# EvaluationBoard.net
KiCad netlist of a schematic drawn in EAGLE
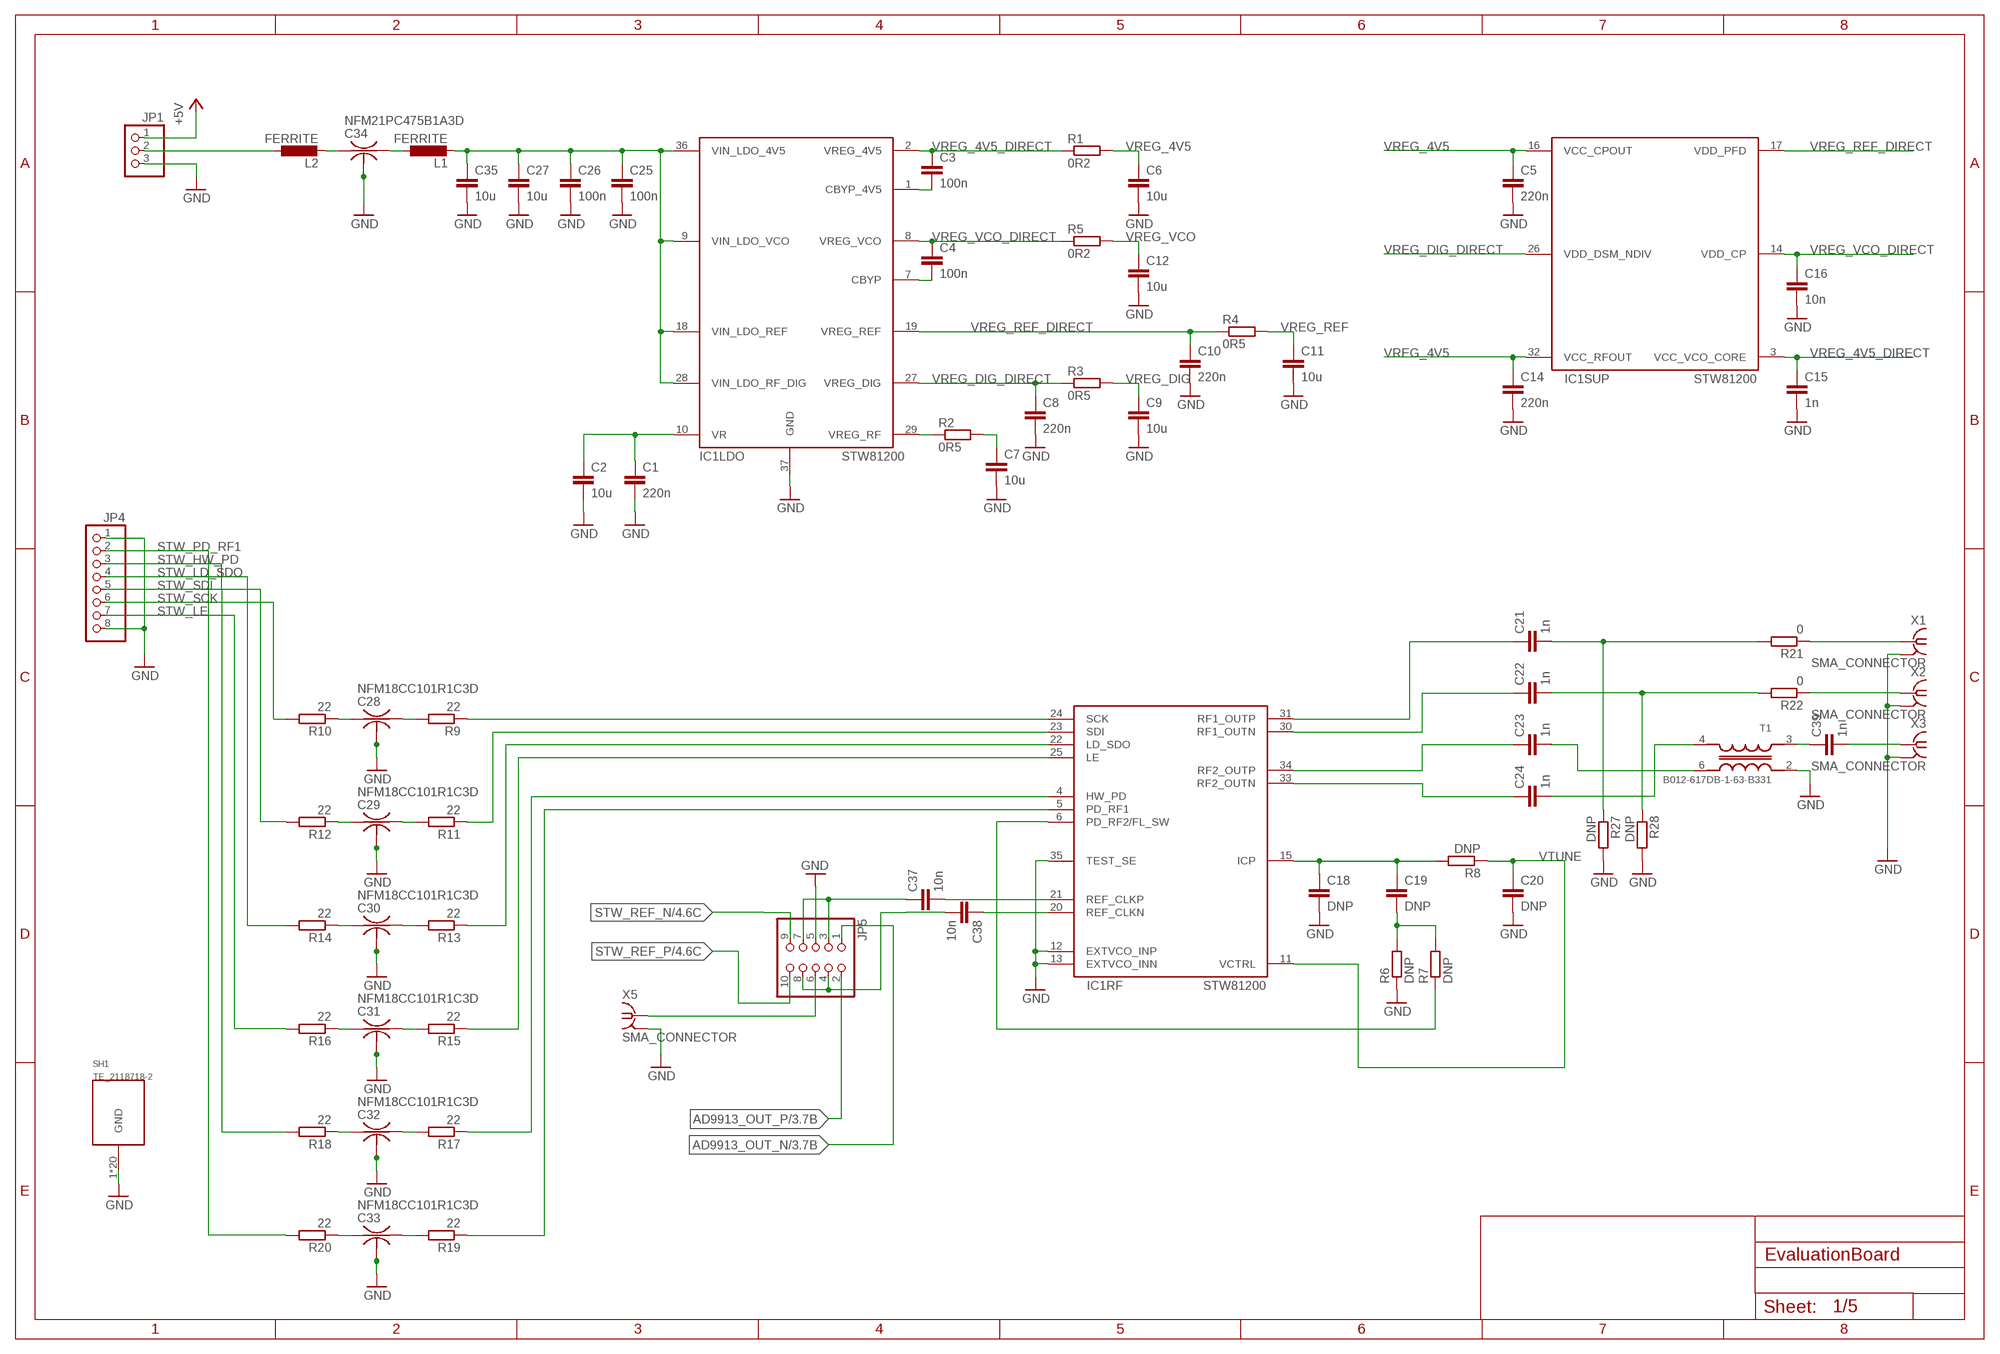
[diagram p0: schematic, sheet 1]
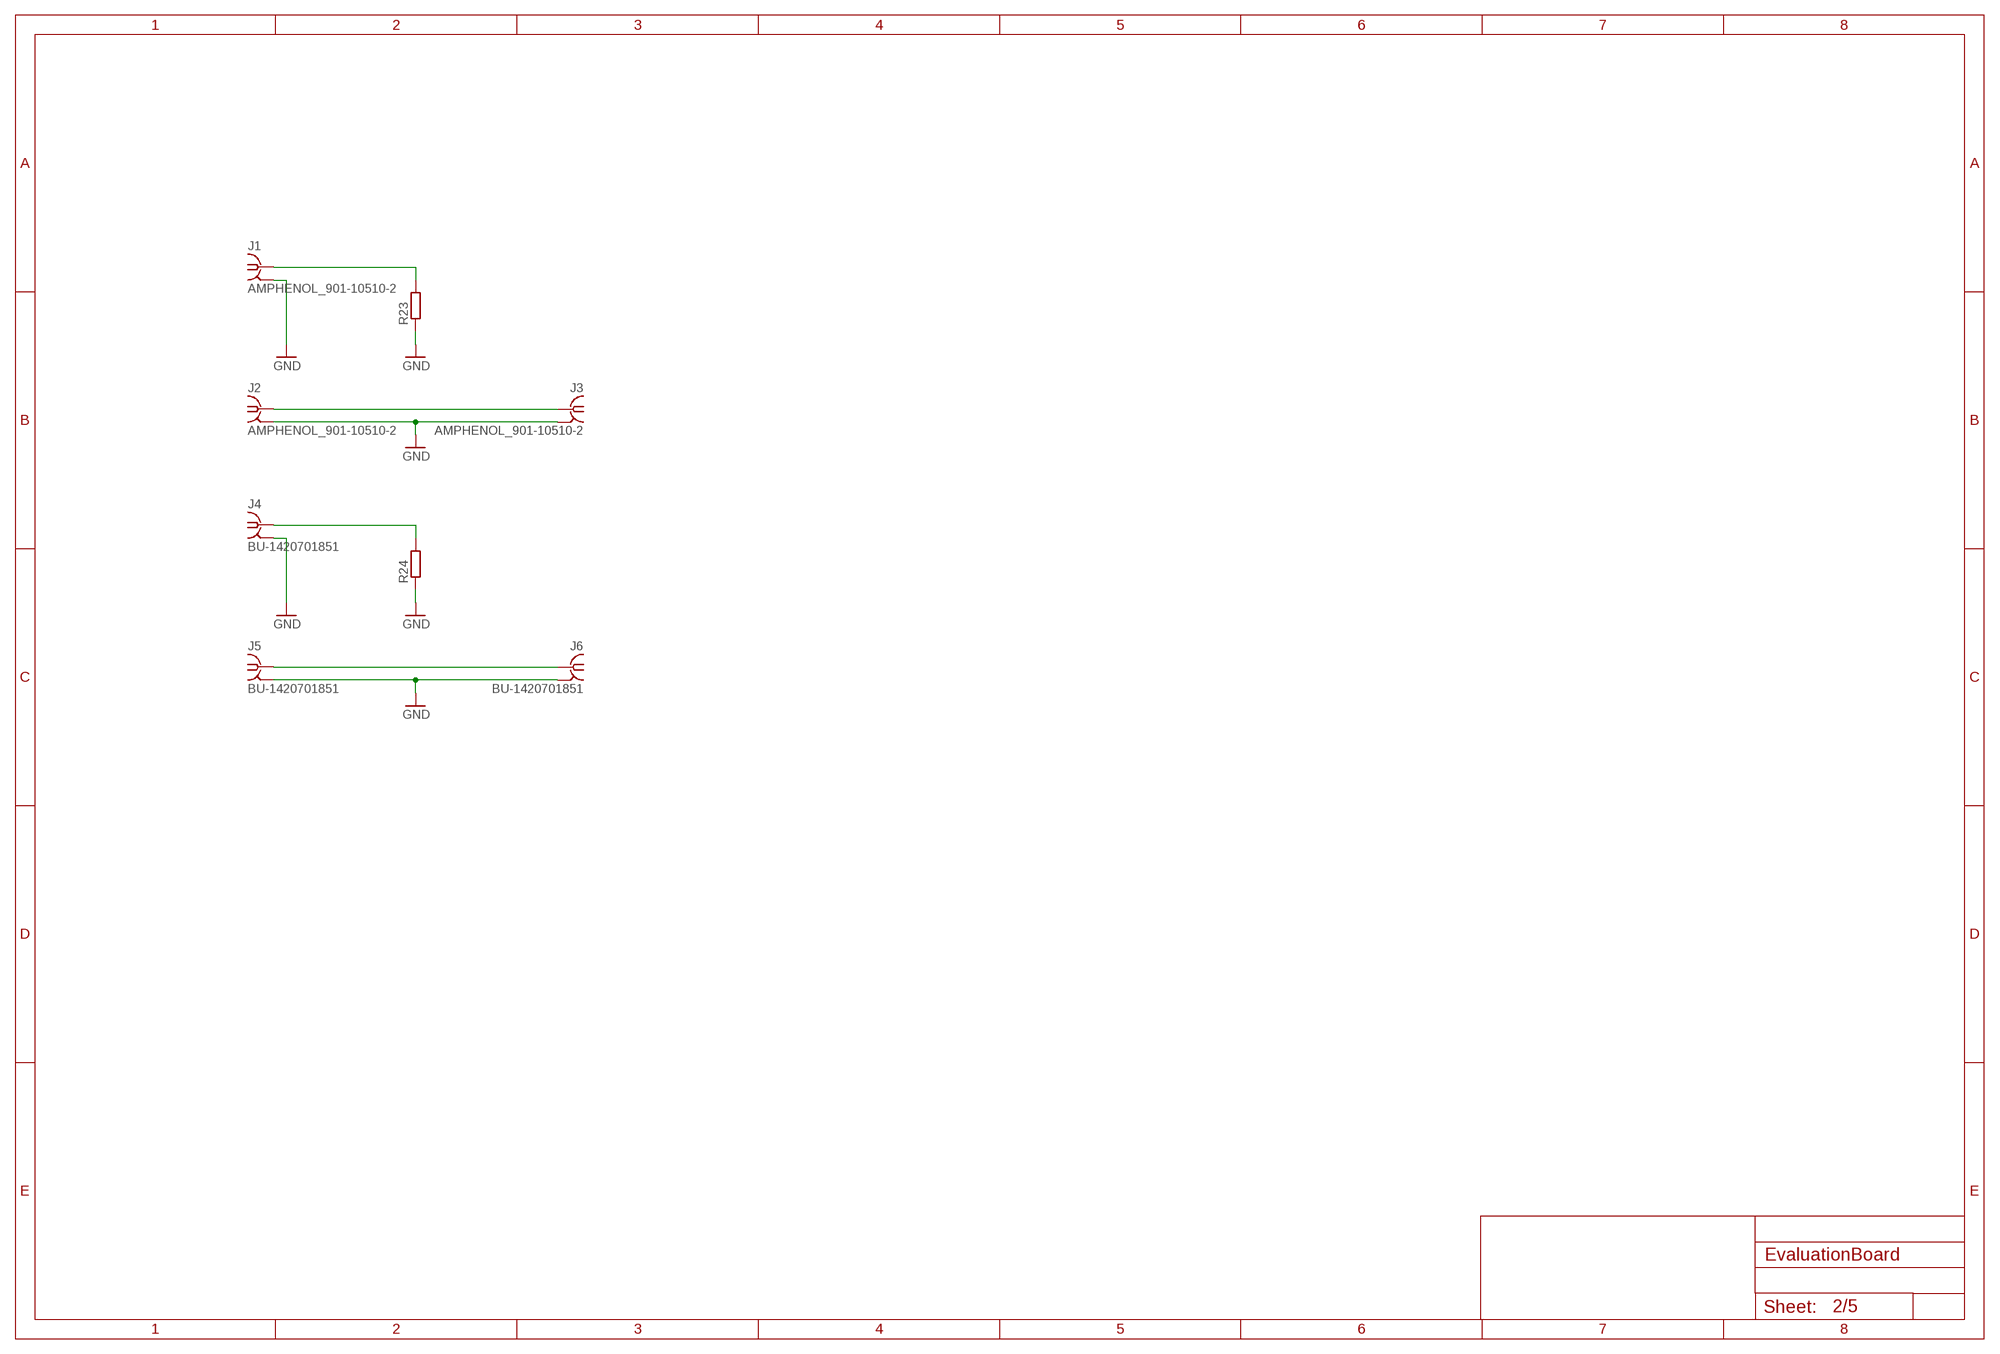
[diagram p1: schematic, sheet 2]
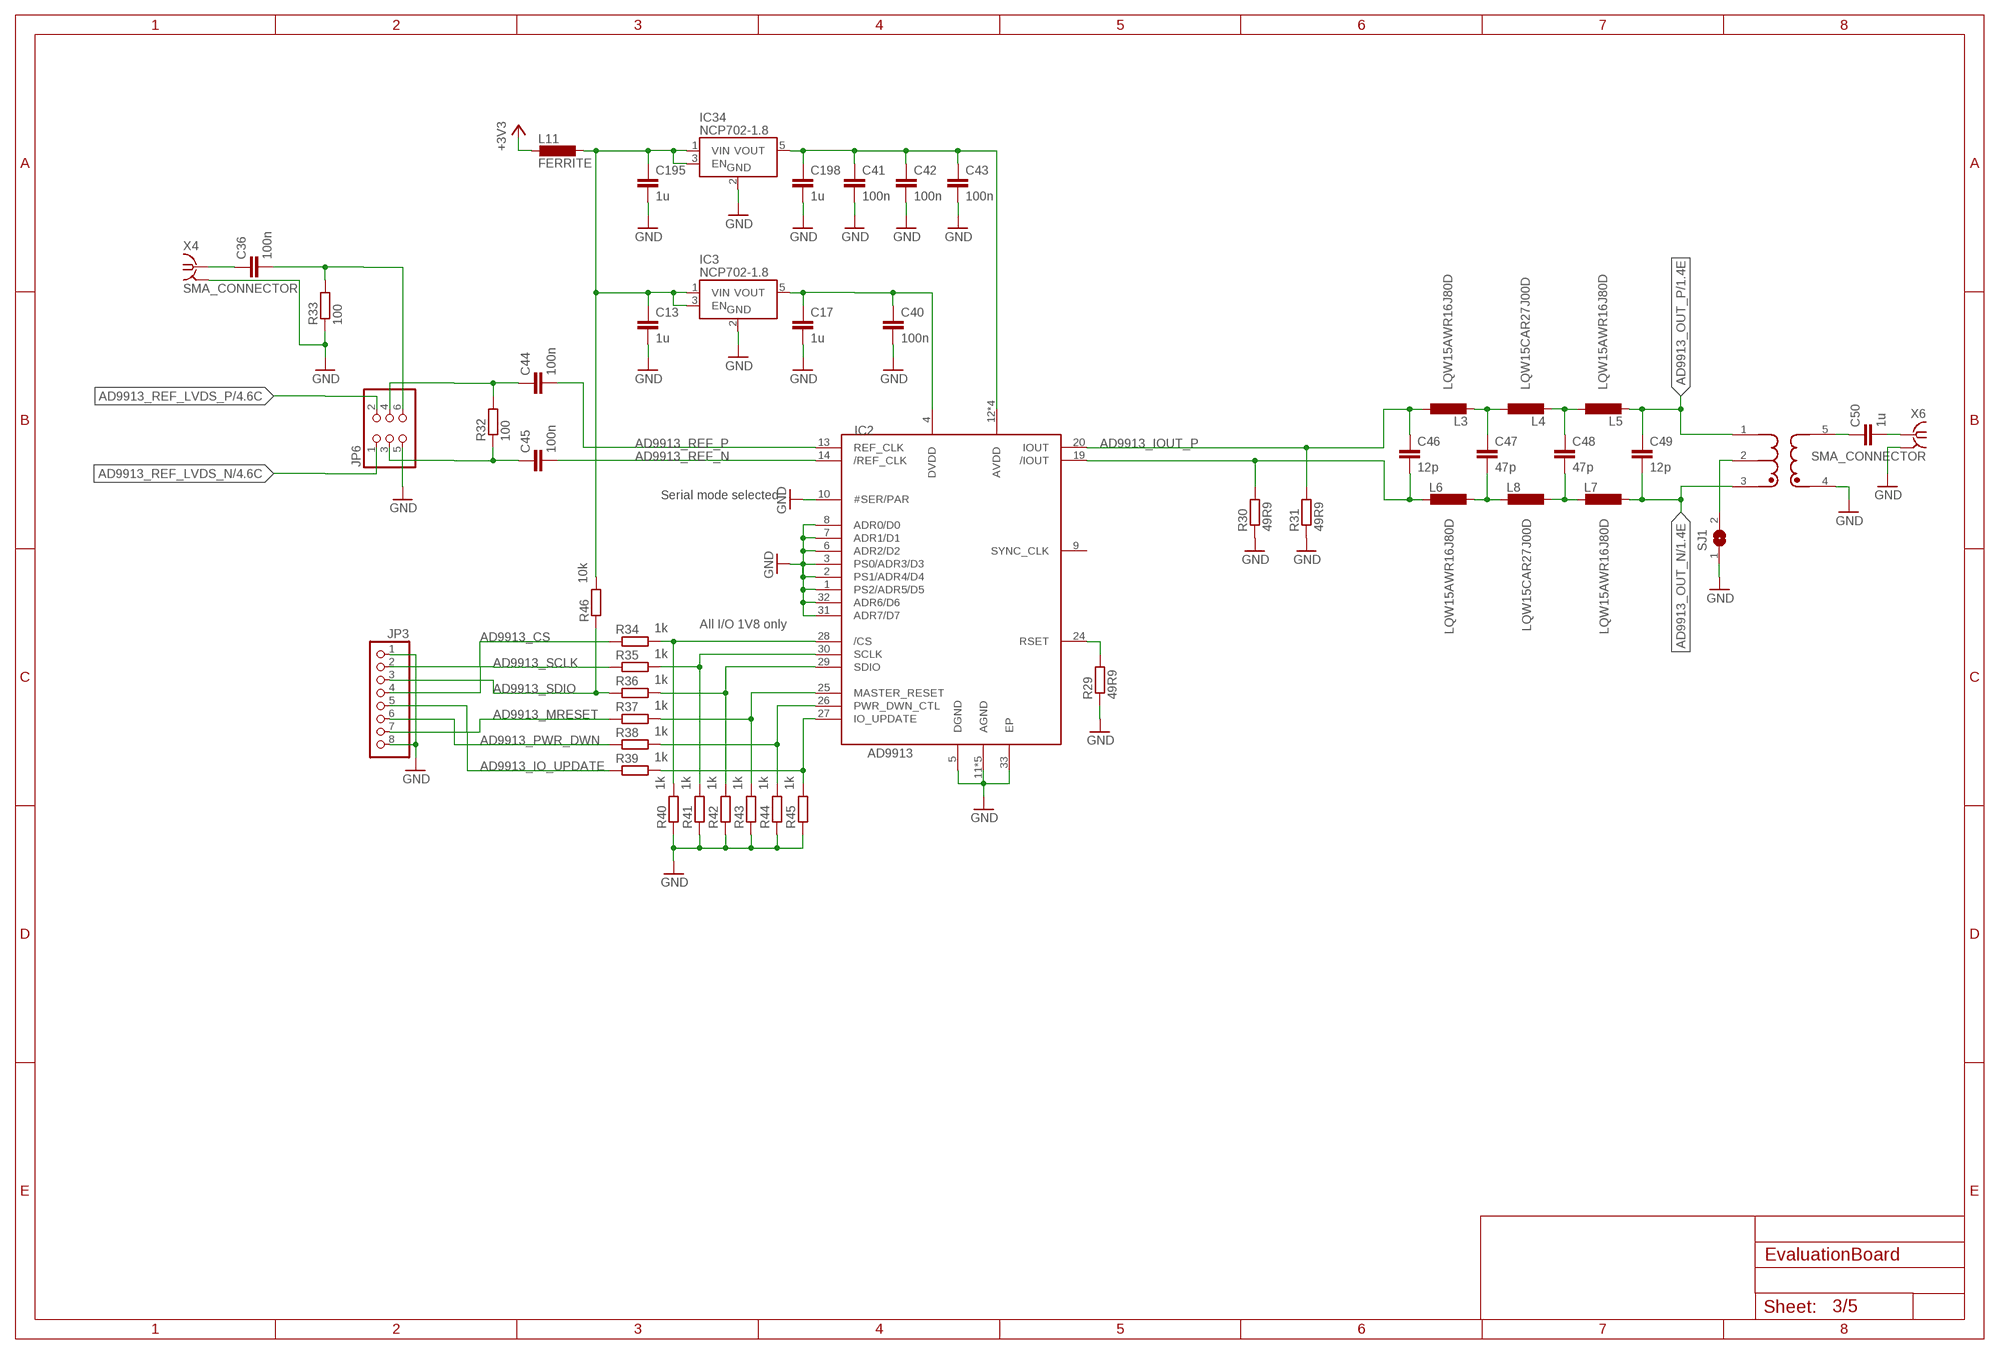
[diagram p2: schematic, sheet 3]
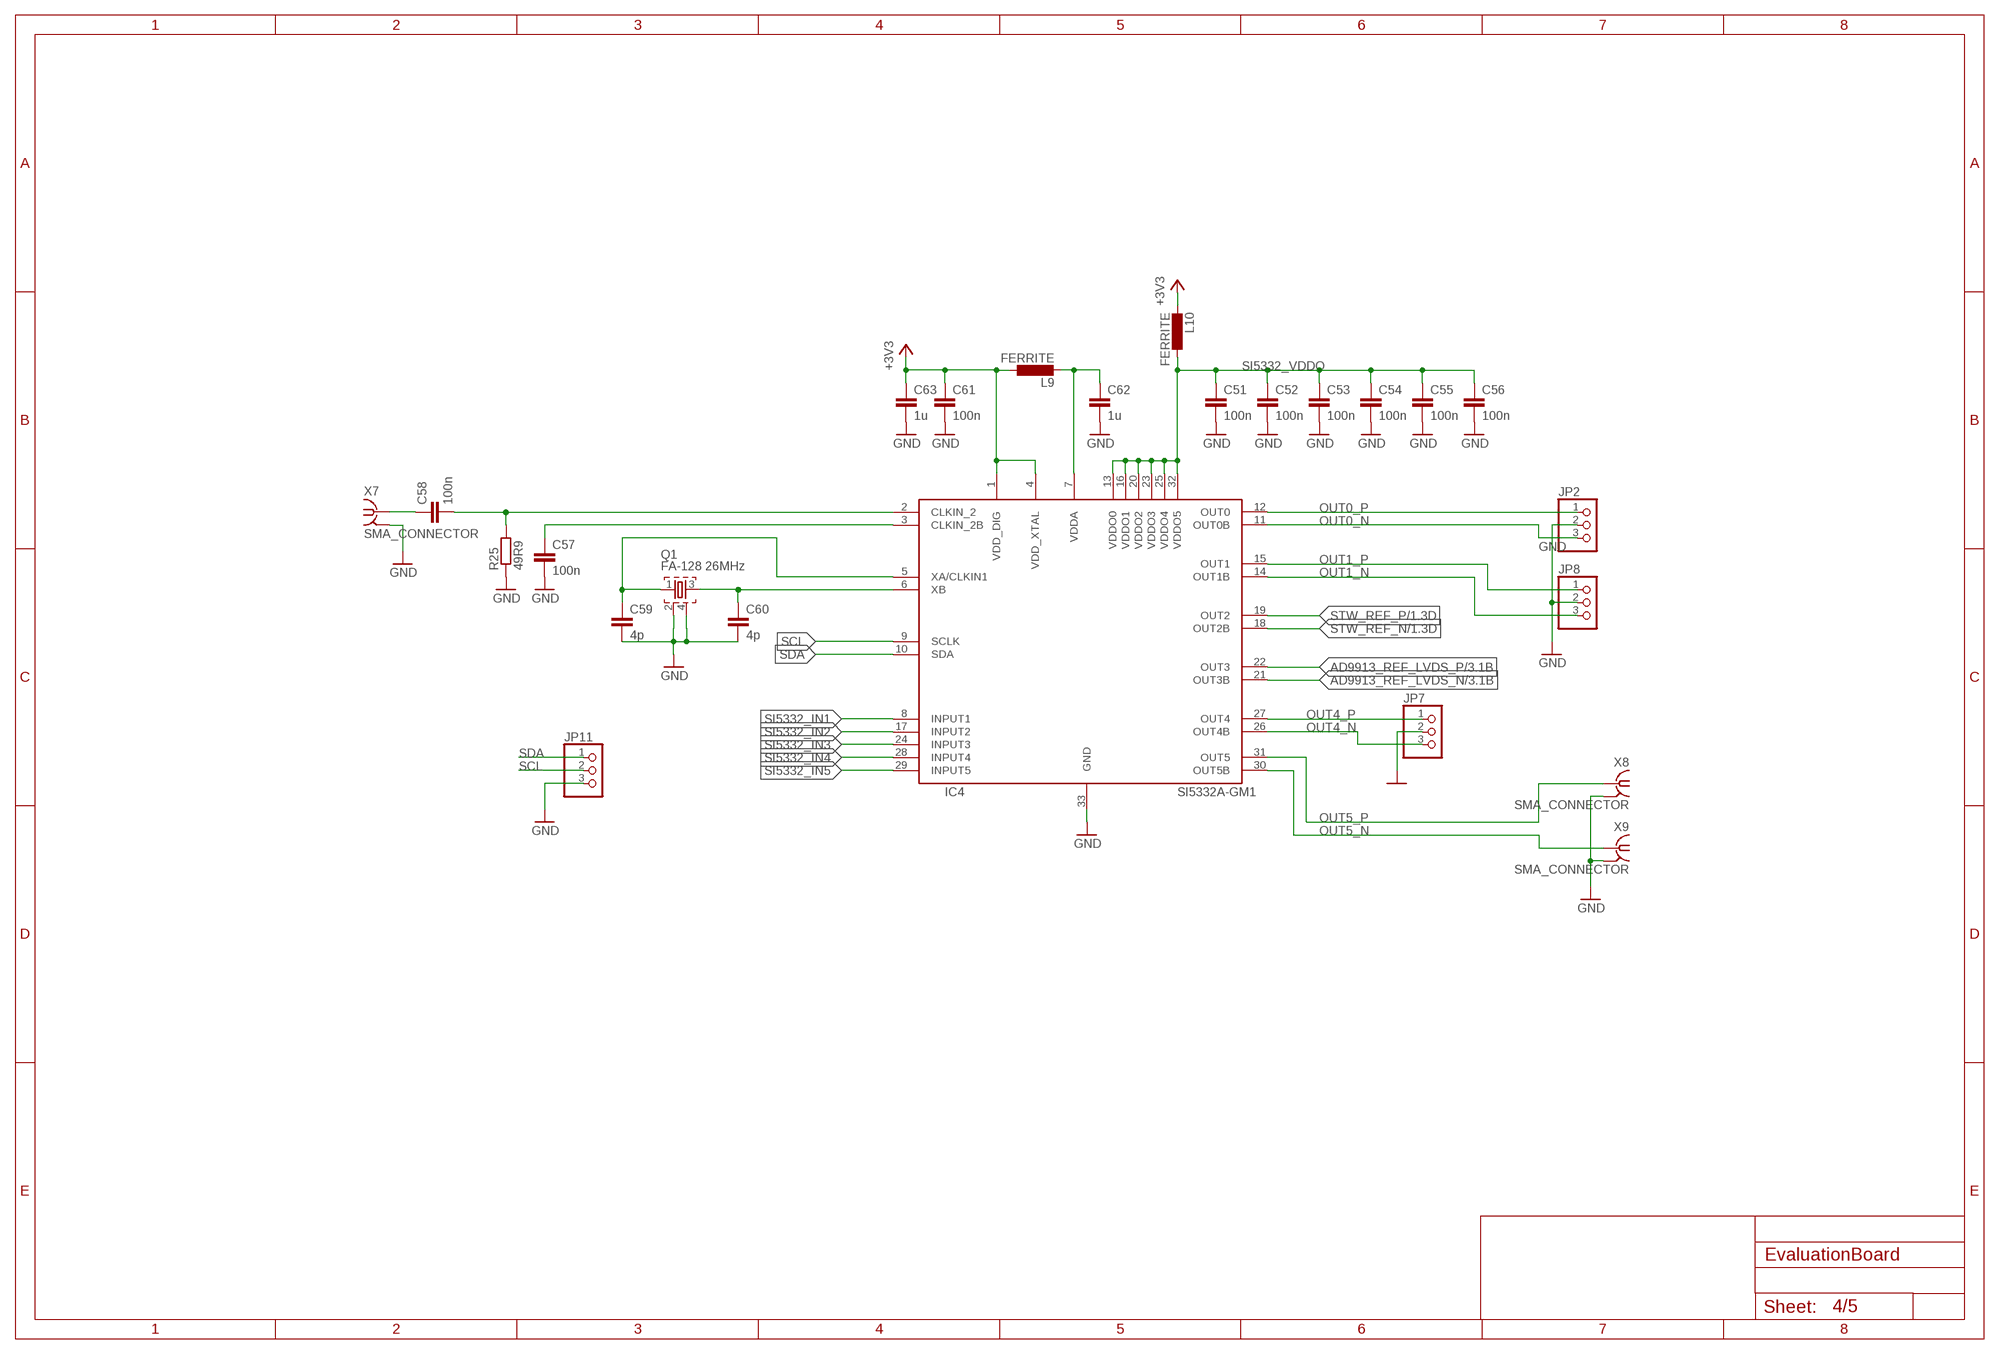
[diagram p3: schematic, sheet 4]
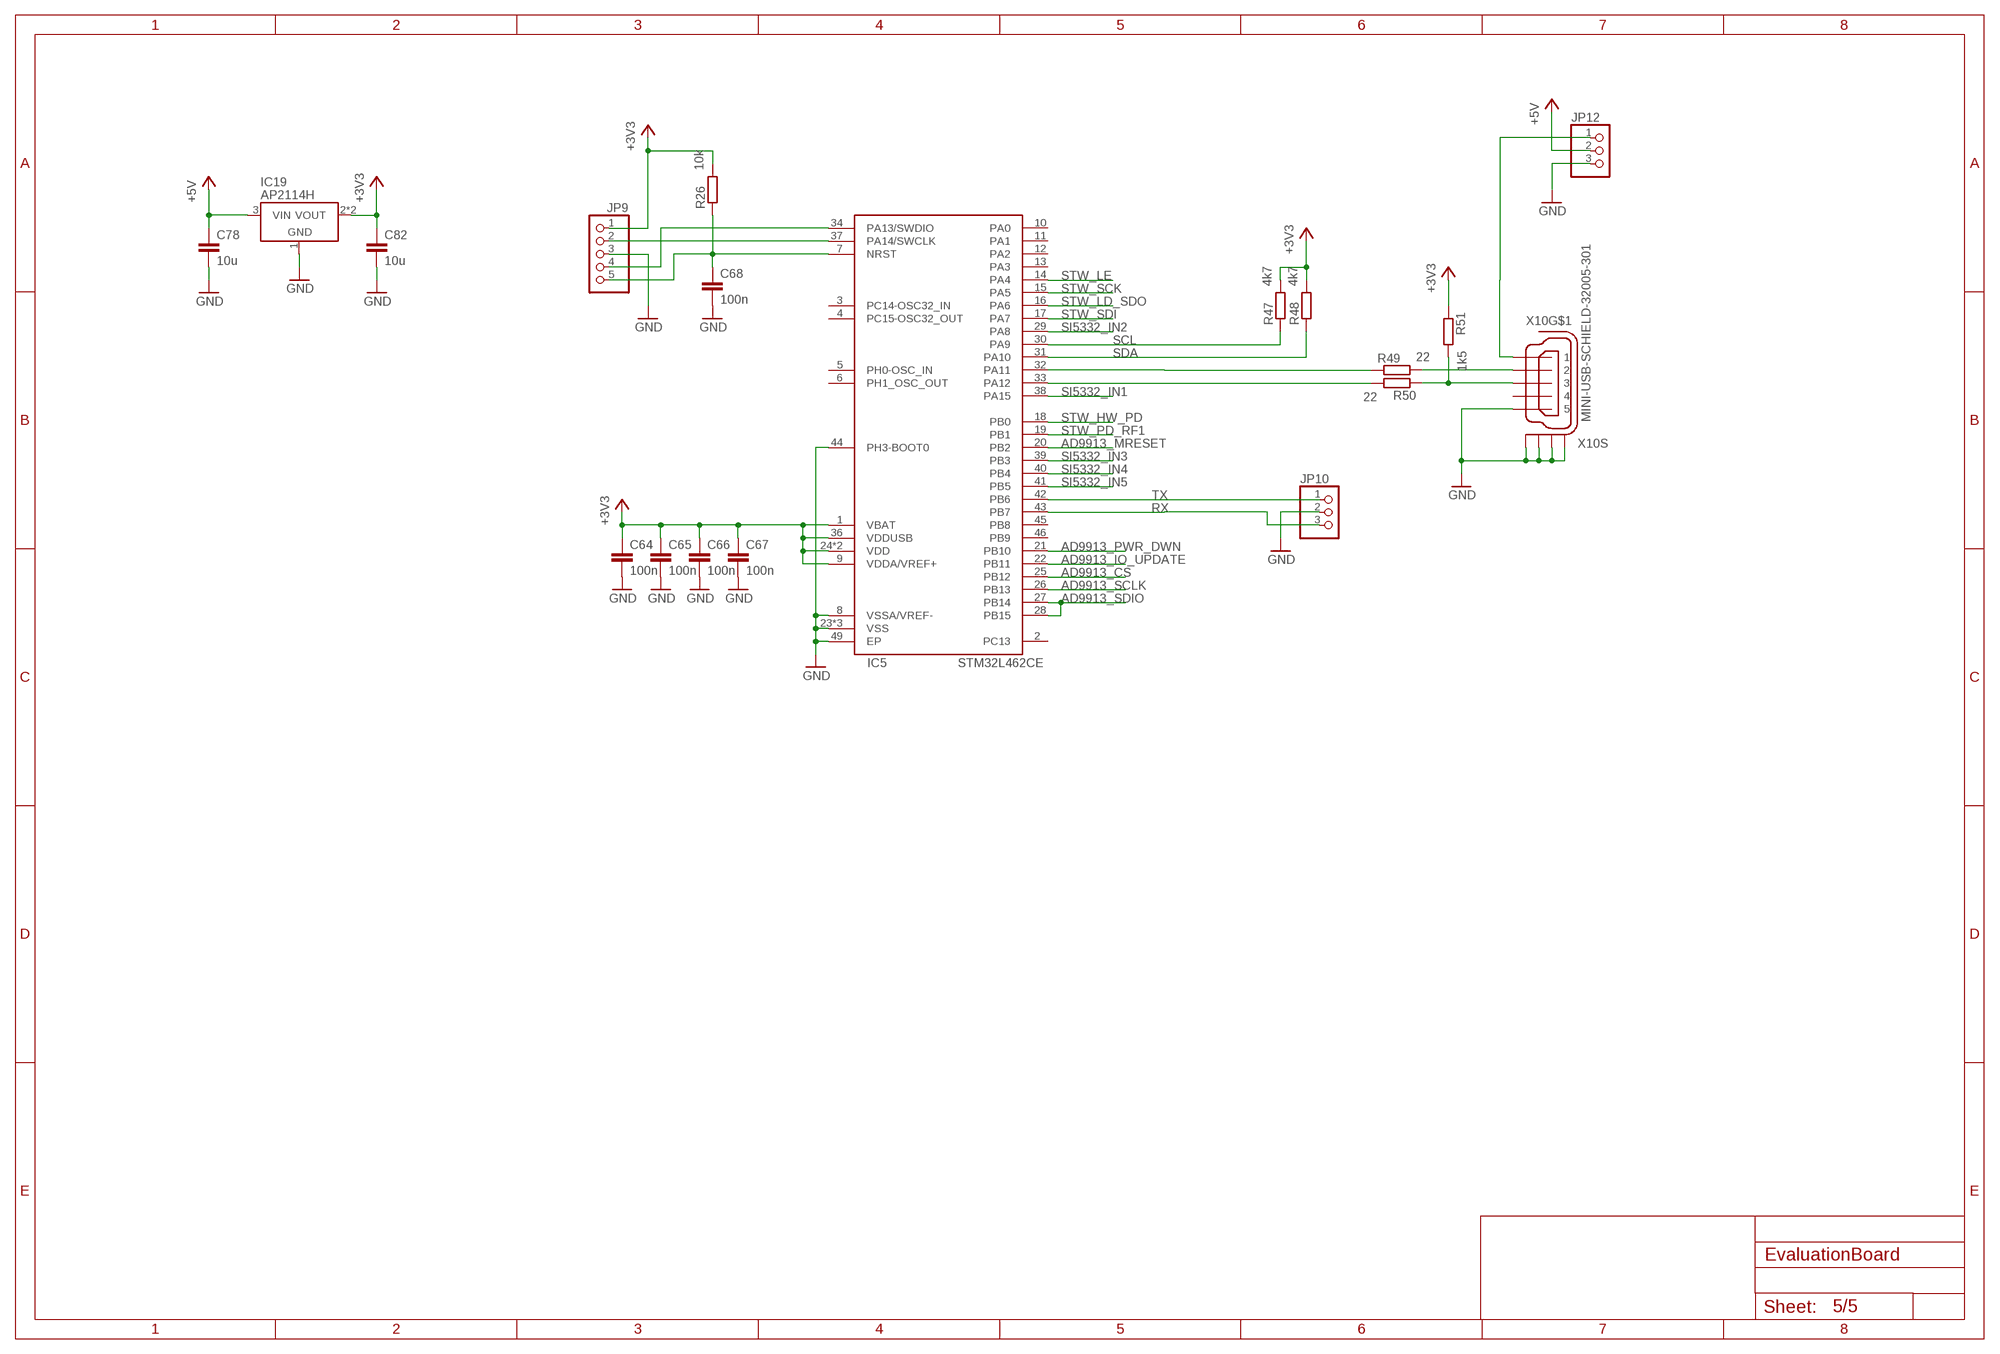
[diagram p4: schematic, sheet 5]

(export (version "E")
  (design (tool "Eeschema 10.0.6"))
  (components
    (comp (ref "C64")
      (value "100n")
      (footprint "eagle-import:C0402")
      (libsource (lib "eagle-import") (part "C-EU?{colon}2C0402"))
    )
    (comp (ref "C65")
      (value "100n")
      (footprint "eagle-import:C0402")
      (libsource (lib "eagle-import") (part "C-EU?{colon}2C0402"))
    )
    (comp (ref "C66")
      (value "100n")
      (footprint "eagle-import:C0402")
      (libsource (lib "eagle-import") (part "C-EU?{colon}2C0402"))
    )
    (comp (ref "C67")
      (value "100n")
      (footprint "eagle-import:C0402")
      (libsource (lib "eagle-import") (part "C-EU?{colon}2C0402"))
    )
    (comp (ref "C68")
      (value "100n")
      (footprint "eagle-import:C0402")
      (libsource (lib "eagle-import") (part "C-EU?{colon}2C0402"))
    )
    (comp (ref "C78")
      (value "10u")
      (footprint "eagle-import:C1206")
      (libsource (lib "eagle-import") (part "C-EUC1206"))
    )
    (comp (ref "C82")
      (value "10u")
      (footprint "eagle-import:C1206")
      (libsource (lib "eagle-import") (part "C-EUC1206"))
    )
    (comp (ref "IC5")
      (value "STM32L462CE")
      (footprint "eagle-import:QFN50P700X700X60-49T560N")
      (libsource (lib "eagle-import") (part "STM32L462CE"))
    )
    (comp (ref "IC19")
      (value "AP2114H")
      (footprint "eagle-import:SOT230P700X180-4")
      (libsource (lib "eagle-import") (part "AP2114H"))
    )
    (comp (ref "JP9")
      (value "PINHD-1X5")
      (footprint "eagle-import:1X05")
      (libsource (lib "eagle-import") (part "PINHD-1X5"))
    )
    (comp (ref "JP10")
      (value "PINHD-1X3")
      (footprint "eagle-import:1X03")
      (libsource (lib "eagle-import") (part "PINHD-1X3"))
    )
    (comp (ref "JP12")
      (value "PINHD-1X3")
      (footprint "eagle-import:1X03")
      (libsource (lib "eagle-import") (part "PINHD-1X3"))
    )
    (comp (ref "R26")
      (value "10k")
      (footprint "eagle-import:R0402")
      (libsource (lib "eagle-import") (part "R-EU_R0402"))
    )
    (comp (ref "R47")
      (value "4k7")
      (footprint "eagle-import:R0402")
      (libsource (lib "eagle-import") (part "R-EU_R0402"))
    )
    (comp (ref "R48")
      (value "4k7")
      (footprint "eagle-import:R0402")
      (libsource (lib "eagle-import") (part "R-EU_R0402"))
    )
    (comp (ref "R49")
      (value "22")
      (footprint "eagle-import:R0402")
      (libsource (lib "eagle-import") (part "R-EU_R0402"))
    )
    (comp (ref "R50")
      (value "22")
      (footprint "eagle-import:R0402")
      (libsource (lib "eagle-import") (part "R-EU_R0402"))
    )
    (comp (ref "R51")
      (value "1k5")
      (footprint "eagle-import:R0402")
      (libsource (lib "eagle-import") (part "R-EU_R0402"))
    )
    (comp (ref "X10")
      (value "MINI-USB-SCHIELD-32005-301")
      (footprint "eagle-import:32005-301")
      (libsource (lib "eagle-import") (part "MINI-USB-SCHIELD-32005-301"))
    )
    (comp (ref "B1")
      (value "ETC1-1T-2")
      (footprint "eagle-import:SM-22")
      (libsource (lib "eagle-import") (part "ETC1-1T"))
    )
    (comp (ref "C13")
      (value "1u")
      (footprint "eagle-import:C0402")
      (libsource (lib "eagle-import") (part "C-EU?{colon}2C0402"))
    )
    (comp (ref "C17")
      (value "1u")
      (footprint "eagle-import:C0402")
      (libsource (lib "eagle-import") (part "C-EU?{colon}2C0402"))
    )
    (comp (ref "C36")
      (value "100n")
      (footprint "eagle-import:C0402")
      (libsource (lib "eagle-import") (part "C-EU?{colon}2C0402"))
    )
    (comp (ref "C40")
      (value "100n")
      (footprint "eagle-import:C0402")
      (libsource (lib "eagle-import") (part "C-EU?{colon}2C0402"))
    )
    (comp (ref "C41")
      (value "100n")
      (footprint "eagle-import:C0402")
      (libsource (lib "eagle-import") (part "C-EU?{colon}2C0402"))
    )
    (comp (ref "C42")
      (value "100n")
      (footprint "eagle-import:C0402")
      (libsource (lib "eagle-import") (part "C-EU?{colon}2C0402"))
    )
    (comp (ref "C43")
      (value "100n")
      (footprint "eagle-import:C0402")
      (libsource (lib "eagle-import") (part "C-EU?{colon}2C0402"))
    )
    (comp (ref "C44")
      (value "100n")
      (footprint "eagle-import:C0402")
      (libsource (lib "eagle-import") (part "C-EU?{colon}2C0402"))
    )
    (comp (ref "C45")
      (value "100n")
      (footprint "eagle-import:C0402")
      (libsource (lib "eagle-import") (part "C-EU?{colon}2C0402"))
    )
    (comp (ref "C46")
      (value "12p")
      (footprint "eagle-import:C0402")
      (libsource (lib "eagle-import") (part "C-EU?{colon}2C0402"))
    )
    (comp (ref "C47")
      (value "47p")
      (footprint "eagle-import:C0402")
      (libsource (lib "eagle-import") (part "C-EU?{colon}2C0402"))
    )
    (comp (ref "C48")
      (value "47p")
      (footprint "eagle-import:C0402")
      (libsource (lib "eagle-import") (part "C-EU?{colon}2C0402"))
    )
    (comp (ref "C49")
      (value "12p")
      (footprint "eagle-import:C0402")
      (libsource (lib "eagle-import") (part "C-EU?{colon}2C0402"))
    )
    (comp (ref "C50")
      (value "1u")
      (footprint "eagle-import:C0402")
      (libsource (lib "eagle-import") (part "C-EU?{colon}2C0402"))
    )
    (comp (ref "C195")
      (value "1u")
      (footprint "eagle-import:C0402")
      (libsource (lib "eagle-import") (part "C-EU?{colon}2C0402"))
    )
    (comp (ref "C198")
      (value "1u")
      (footprint "eagle-import:C0402")
      (libsource (lib "eagle-import") (part "C-EU?{colon}2C0402"))
    )
    (comp (ref "IC2")
      (value "AD9913")
      (footprint "eagle-import:QFN50P500X500X80-33T310")
      (libsource (lib "eagle-import") (part "AD9913"))
    )
    (comp (ref "IC3")
      (value "NCP702-1.8")
      (footprint "eagle-import:SOT95P240X110-5")
      (libsource (lib "eagle-import") (part "NCP702"))
    )
    (comp (ref "IC34")
      (value "NCP702-1.8")
      (footprint "eagle-import:SOT95P240X110-5")
      (libsource (lib "eagle-import") (part "NCP702"))
    )
    (comp (ref "JP3")
      (value "PINHD-1X8")
      (footprint "eagle-import:1X08")
      (libsource (lib "eagle-import") (part "PINHD-1X8"))
    )
    (comp (ref "JP6")
      (value "PINHD-2X3")
      (footprint "eagle-import:2X03")
      (libsource (lib "eagle-import") (part "PINHD-2X3"))
    )
    (comp (ref "L3")
      (value "LQW15AWR16J80D")
      (footprint "eagle-import:L0402")
      (libsource (lib "eagle-import") (part "INDUCTOR0402"))
    )
    (comp (ref "L4")
      (value "LQW15CAR27J00D")
      (footprint "eagle-import:L0402")
      (libsource (lib "eagle-import") (part "INDUCTOR0402"))
    )
    (comp (ref "L5")
      (value "LQW15AWR16J80D")
      (footprint "eagle-import:L0402")
      (libsource (lib "eagle-import") (part "INDUCTOR0402"))
    )
    (comp (ref "L6")
      (value "LQW15AWR16J80D")
      (footprint "eagle-import:L0402")
      (libsource (lib "eagle-import") (part "INDUCTOR0402"))
    )
    (comp (ref "L7")
      (value "LQW15AWR16J80D")
      (footprint "eagle-import:L0402")
      (libsource (lib "eagle-import") (part "INDUCTOR0402"))
    )
    (comp (ref "L8")
      (value "LQW15CAR27J00D")
      (footprint "eagle-import:L0402")
      (libsource (lib "eagle-import") (part "INDUCTOR0402"))
    )
    (comp (ref "L11")
      (value "FERRITE")
      (footprint "eagle-import:R0402")
      (libsource (lib "eagle-import") (part "FERRITE"))
    )
    (comp (ref "R29")
      (value "49R9")
      (footprint "eagle-import:R0402")
      (libsource (lib "eagle-import") (part "R-EU_R0402"))
    )
    (comp (ref "R30")
      (value "49R9")
      (footprint "eagle-import:R0402")
      (libsource (lib "eagle-import") (part "R-EU_R0402"))
    )
    (comp (ref "R31")
      (value "49R9")
      (footprint "eagle-import:R0402")
      (libsource (lib "eagle-import") (part "R-EU_R0402"))
    )
    (comp (ref "R32")
      (value "100")
      (footprint "eagle-import:R0402")
      (libsource (lib "eagle-import") (part "R-EU_R0402"))
    )
    (comp (ref "R33")
      (value "100")
      (footprint "eagle-import:R0402")
      (libsource (lib "eagle-import") (part "R-EU_R0402"))
    )
    (comp (ref "R34")
      (value "1k")
      (footprint "eagle-import:R0402")
      (libsource (lib "eagle-import") (part "R-EU_R0402"))
    )
    (comp (ref "R35")
      (value "1k")
      (footprint "eagle-import:R0402")
      (libsource (lib "eagle-import") (part "R-EU_R0402"))
    )
    (comp (ref "R36")
      (value "1k")
      (footprint "eagle-import:R0402")
      (libsource (lib "eagle-import") (part "R-EU_R0402"))
    )
    (comp (ref "R37")
      (value "1k")
      (footprint "eagle-import:R0402")
      (libsource (lib "eagle-import") (part "R-EU_R0402"))
    )
    (comp (ref "R38")
      (value "1k")
      (footprint "eagle-import:R0402")
      (libsource (lib "eagle-import") (part "R-EU_R0402"))
    )
    (comp (ref "R39")
      (value "1k")
      (footprint "eagle-import:R0402")
      (libsource (lib "eagle-import") (part "R-EU_R0402"))
    )
    (comp (ref "R40")
      (value "1k")
      (footprint "eagle-import:R0402")
      (libsource (lib "eagle-import") (part "R-EU_R0402"))
    )
    (comp (ref "R41")
      (value "1k")
      (footprint "eagle-import:R0402")
      (libsource (lib "eagle-import") (part "R-EU_R0402"))
    )
    (comp (ref "R42")
      (value "1k")
      (footprint "eagle-import:R0402")
      (libsource (lib "eagle-import") (part "R-EU_R0402"))
    )
    (comp (ref "R43")
      (value "1k")
      (footprint "eagle-import:R0402")
      (libsource (lib "eagle-import") (part "R-EU_R0402"))
    )
    (comp (ref "R44")
      (value "1k")
      (footprint "eagle-import:R0402")
      (libsource (lib "eagle-import") (part "R-EU_R0402"))
    )
    (comp (ref "R45")
      (value "1k")
      (footprint "eagle-import:R0402")
      (libsource (lib "eagle-import") (part "R-EU_R0402"))
    )
    (comp (ref "R46")
      (value "10k")
      (footprint "eagle-import:R0402")
      (libsource (lib "eagle-import") (part "R-EU_R0402"))
    )
    (comp (ref "SJ1") (value "SJ") (footprint "eagle-import:SJ") (libsource (lib "eagle-import") (part "SJ")))
    (comp (ref "X4")
      (value "SMA_CONNECTOR")
      (footprint "eagle-import:J502-ND-142-0711-821_826")
      (libsource (lib "eagle-import") (part "SMA_CONNECTOR"))
    )
    (comp (ref "X6")
      (value "SMA_CONNECTOR")
      (footprint "eagle-import:J502-ND-142-0711-821_826")
      (libsource (lib "eagle-import") (part "SMA_CONNECTOR"))
    )
    (comp (ref "C1")
      (value "220n")
      (footprint "eagle-import:C0402")
      (libsource (lib "eagle-import") (part "C-EUC0402"))
    )
    (comp (ref "C2")
      (value "10u")
      (footprint "eagle-import:C0603")
      (libsource (lib "eagle-import") (part "rcl_334_C-EUC0603"))
    )
    (comp (ref "C3")
      (value "100n")
      (footprint "eagle-import:C0402")
      (libsource (lib "eagle-import") (part "C-EUC0402"))
    )
    (comp (ref "C4")
      (value "100n")
      (footprint "eagle-import:C0402")
      (libsource (lib "eagle-import") (part "C-EUC0402"))
    )
    (comp (ref "C5")
      (value "220n")
      (footprint "eagle-import:C0402")
      (libsource (lib "eagle-import") (part "C-EUC0402"))
    )
    (comp (ref "C6")
      (value "10u")
      (footprint "eagle-import:C0603")
      (libsource (lib "eagle-import") (part "rcl_334_C-EUC0603"))
    )
    (comp (ref "C7")
      (value "10u")
      (footprint "eagle-import:C0603")
      (libsource (lib "eagle-import") (part "rcl_334_C-EUC0603"))
    )
    (comp (ref "C8")
      (value "220n")
      (footprint "eagle-import:C0402")
      (libsource (lib "eagle-import") (part "C-EUC0402"))
    )
    (comp (ref "C9")
      (value "10u")
      (footprint "eagle-import:C0603")
      (libsource (lib "eagle-import") (part "rcl_334_C-EUC0603"))
    )
    (comp (ref "C10")
      (value "220n")
      (footprint "eagle-import:C0402")
      (libsource (lib "eagle-import") (part "C-EUC0402"))
    )
    (comp (ref "C11")
      (value "10u")
      (footprint "eagle-import:C0603")
      (libsource (lib "eagle-import") (part "rcl_334_C-EUC0603"))
    )
    (comp (ref "C12")
      (value "10u")
      (footprint "eagle-import:C0603")
      (libsource (lib "eagle-import") (part "rcl_334_C-EUC0603"))
    )
    (comp (ref "C14")
      (value "220n")
      (footprint "eagle-import:C0402")
      (libsource (lib "eagle-import") (part "C-EUC0402"))
    )
    (comp (ref "C15")
      (value "1n")
      (footprint "eagle-import:C0402")
      (libsource (lib "eagle-import") (part "C-EUC0402"))
    )
    (comp (ref "C16")
      (value "10n")
      (footprint "eagle-import:C0402")
      (libsource (lib "eagle-import") (part "C-EUC0402"))
    )
    (comp (ref "C18")
      (value "DNP")
      (footprint "eagle-import:C0402")
      (libsource (lib "eagle-import") (part "C-EUC0402"))
    )
    (comp (ref "C19")
      (value "DNP")
      (footprint "eagle-import:C0402")
      (libsource (lib "eagle-import") (part "C-EUC0402"))
    )
    (comp (ref "C20")
      (value "DNP")
      (footprint "eagle-import:C0402")
      (libsource (lib "eagle-import") (part "C-EUC0402"))
    )
    (comp (ref "C21")
      (value "1n")
      (footprint "eagle-import:C0402")
      (libsource (lib "eagle-import") (part "C-EUC0402"))
    )
    (comp (ref "C22")
      (value "1n")
      (footprint "eagle-import:C0402")
      (libsource (lib "eagle-import") (part "C-EUC0402"))
    )
    (comp (ref "C23")
      (value "1n")
      (footprint "eagle-import:C0402")
      (libsource (lib "eagle-import") (part "C-EUC0402"))
    )
    (comp (ref "C24")
      (value "1n")
      (footprint "eagle-import:C0402")
      (libsource (lib "eagle-import") (part "C-EUC0402"))
    )
    (comp (ref "C25")
      (value "100n")
      (footprint "eagle-import:C0402")
      (libsource (lib "eagle-import") (part "C-EUC0402"))
    )
    (comp (ref "C26")
      (value "100n")
      (footprint "eagle-import:C0402")
      (libsource (lib "eagle-import") (part "C-EUC0402"))
    )
    (comp (ref "C27")
      (value "10u")
      (footprint "eagle-import:C0603")
      (libsource (lib "eagle-import") (part "rcl_334_C-EUC0603"))
    )
    (comp (ref "C28")
      (value "NFM18CC101R1C3D")
      (footprint "eagle-import:NFM18PC")
      (libsource (lib "eagle-import") (part "NFM18CC101R1C3D"))
    )
    (comp (ref "C29")
      (value "NFM18CC101R1C3D")
      (footprint "eagle-import:NFM18PC")
      (libsource (lib "eagle-import") (part "NFM18CC101R1C3D"))
    )
    (comp (ref "C30")
      (value "NFM18CC101R1C3D")
      (footprint "eagle-import:NFM18PC")
      (libsource (lib "eagle-import") (part "NFM18CC101R1C3D"))
    )
    (comp (ref "C31")
      (value "NFM18CC101R1C3D")
      (footprint "eagle-import:NFM18PC")
      (libsource (lib "eagle-import") (part "NFM18CC101R1C3D"))
    )
    (comp (ref "C32")
      (value "NFM18CC101R1C3D")
      (footprint "eagle-import:NFM18PC")
      (libsource (lib "eagle-import") (part "NFM18CC101R1C3D"))
    )
    (comp (ref "C33")
      (value "NFM18CC101R1C3D")
      (footprint "eagle-import:NFM18PC")
      (libsource (lib "eagle-import") (part "NFM18CC101R1C3D"))
    )
    (comp (ref "C34")
      (value "NFM21PC475B1A3D")
      (footprint "eagle-import:NFM21PC")
      (libsource (lib "eagle-import") (part "NFM21PC475B1A3D"))
    )
    (comp (ref "C35")
      (value "10u")
      (footprint "eagle-import:C0603")
      (libsource (lib "eagle-import") (part "rcl_334_C-EUC0603"))
    )
    (comp (ref "C37")
      (value "10n")
      (footprint "eagle-import:C0402")
      (libsource (lib "eagle-import") (part "C-EUC0402"))
    )
    (comp (ref "C38")
      (value "10n")
      (footprint "eagle-import:C0402")
      (libsource (lib "eagle-import") (part "C-EUC0402"))
    )
    (comp (ref "C39")
      (value "1n")
      (footprint "eagle-import:C0402")
      (libsource (lib "eagle-import") (part "C-EUC0402"))
    )
    (comp (ref "IC1")
      (value "STW81200")
      (footprint "eagle-import:QFN50P600X600X100-37T410N")
      (libsource (lib "eagle-import") (part "STW81200"))
    )
    (comp (ref "JP1")
      (value "PINHD-1X3")
      (footprint "eagle-import:1X03")
      (libsource (lib "eagle-import") (part "PINHD-1X3"))
    )
    (comp (ref "JP4")
      (value "PINHD-1X8")
      (footprint "eagle-import:1X08")
      (libsource (lib "eagle-import") (part "PINHD-1X8"))
    )
    (comp (ref "JP5")
      (value "PINHD-2X5")
      (footprint "eagle-import:2X05")
      (libsource (lib "eagle-import") (part "PINHD-2X5"))
    )
    (comp (ref "L1")
      (value "FERRITE")
      (footprint "eagle-import:R0402")
      (libsource (lib "eagle-import") (part "FERRITE"))
    )
    (comp (ref "L2")
      (value "FERRITE")
      (footprint "eagle-import:R0402")
      (libsource (lib "eagle-import") (part "FERRITE"))
    )
    (comp (ref "R1")
      (value "0R2")
      (footprint "eagle-import:R0402")
      (libsource (lib "eagle-import") (part "R-EU_R0402"))
    )
    (comp (ref "R2")
      (value "0R5")
      (footprint "eagle-import:R0402")
      (libsource (lib "eagle-import") (part "R-EU_R0402"))
    )
    (comp (ref "R3")
      (value "0R5")
      (footprint "eagle-import:R0402")
      (libsource (lib "eagle-import") (part "R-EU_R0402"))
    )
    (comp (ref "R4")
      (value "0R5")
      (footprint "eagle-import:R0402")
      (libsource (lib "eagle-import") (part "R-EU_R0402"))
    )
    (comp (ref "R5")
      (value "0R2")
      (footprint "eagle-import:R0402")
      (libsource (lib "eagle-import") (part "R-EU_R0402"))
    )
    (comp (ref "R6")
      (value "DNP")
      (footprint "eagle-import:R0402")
      (libsource (lib "eagle-import") (part "R-EU_R0402"))
    )
    (comp (ref "R7")
      (value "DNP")
      (footprint "eagle-import:R0402")
      (libsource (lib "eagle-import") (part "R-EU_R0402"))
    )
    (comp (ref "R8")
      (value "DNP")
      (footprint "eagle-import:R0402")
      (libsource (lib "eagle-import") (part "R-EU_R0402"))
    )
    (comp (ref "R9")
      (value "22")
      (footprint "eagle-import:R0402")
      (libsource (lib "eagle-import") (part "R-EU_R0402"))
    )
    (comp (ref "R10")
      (value "22")
      (footprint "eagle-import:R0402")
      (libsource (lib "eagle-import") (part "R-EU_R0402"))
    )
    (comp (ref "R11")
      (value "22")
      (footprint "eagle-import:R0402")
      (libsource (lib "eagle-import") (part "R-EU_R0402"))
    )
    (comp (ref "R12")
      (value "22")
      (footprint "eagle-import:R0402")
      (libsource (lib "eagle-import") (part "R-EU_R0402"))
    )
    (comp (ref "R13")
      (value "22")
      (footprint "eagle-import:R0402")
      (libsource (lib "eagle-import") (part "R-EU_R0402"))
    )
    (comp (ref "R14")
      (value "22")
      (footprint "eagle-import:R0402")
      (libsource (lib "eagle-import") (part "R-EU_R0402"))
    )
    (comp (ref "R15")
      (value "22")
      (footprint "eagle-import:R0402")
      (libsource (lib "eagle-import") (part "R-EU_R0402"))
    )
    (comp (ref "R16")
      (value "22")
      (footprint "eagle-import:R0402")
      (libsource (lib "eagle-import") (part "R-EU_R0402"))
    )
    (comp (ref "R17")
      (value "22")
      (footprint "eagle-import:R0402")
      (libsource (lib "eagle-import") (part "R-EU_R0402"))
    )
    (comp (ref "R18")
      (value "22")
      (footprint "eagle-import:R0402")
      (libsource (lib "eagle-import") (part "R-EU_R0402"))
    )
    (comp (ref "R19")
      (value "22")
      (footprint "eagle-import:R0402")
      (libsource (lib "eagle-import") (part "R-EU_R0402"))
    )
    (comp (ref "R20")
      (value "22")
      (footprint "eagle-import:R0402")
      (libsource (lib "eagle-import") (part "R-EU_R0402"))
    )
    (comp (ref "R21")
      (value "0")
      (footprint "eagle-import:R0402")
      (libsource (lib "eagle-import") (part "R-EU_R0402"))
    )
    (comp (ref "R22")
      (value "0")
      (footprint "eagle-import:R0402")
      (libsource (lib "eagle-import") (part "R-EU_R0402"))
    )
    (comp (ref "R27")
      (value "DNP")
      (footprint "eagle-import:R0402")
      (libsource (lib "eagle-import") (part "R-EU_R0402"))
    )
    (comp (ref "R28")
      (value "DNP")
      (footprint "eagle-import:R0402")
      (libsource (lib "eagle-import") (part "R-EU_R0402"))
    )
    (comp (ref "SH1")
      (value "TE_2118718-2")
      (footprint "eagle-import:TE_2118718-2")
      (libsource (lib "eagle-import") (part "TE_2118718-2"))
    )
    (comp (ref "T1")
      (value "B012-617DB-1-63-B331")
      (footprint "eagle-import:EASTEVER_BALUN")
      (libsource (lib "eagle-import") (part "B012-617DB-1-63-B331"))
    )
    (comp (ref "X1")
      (value "SMA_CONNECTOR")
      (footprint "eagle-import:J502-ND-142-0711-821_826")
      (libsource (lib "eagle-import") (part "SMA_CONNECTOR"))
    )
    (comp (ref "X2")
      (value "SMA_CONNECTOR")
      (footprint "eagle-import:J502-ND-142-0711-821_826")
      (libsource (lib "eagle-import") (part "SMA_CONNECTOR"))
    )
    (comp (ref "X3")
      (value "SMA_CONNECTOR")
      (footprint "eagle-import:J502-ND-142-0711-821_826")
      (libsource (lib "eagle-import") (part "SMA_CONNECTOR"))
    )
    (comp (ref "X5")
      (value "SMA_CONNECTOR")
      (footprint "eagle-import:J502-ND-142-0711-821_826")
      (libsource (lib "eagle-import") (part "SMA_CONNECTOR"))
    )
    (comp (ref "J1")
      (value "AMPHENOL_901-10510-2")
      (footprint "eagle-import:AMPHENOL_901-10510-2")
      (libsource (lib "eagle-import") (part "AMPHENOL_901-10510-2"))
    )
    (comp (ref "J2")
      (value "AMPHENOL_901-10510-2")
      (footprint "eagle-import:AMPHENOL_901-10510-2")
      (libsource (lib "eagle-import") (part "AMPHENOL_901-10510-2"))
    )
    (comp (ref "J3")
      (value "AMPHENOL_901-10510-2")
      (footprint "eagle-import:AMPHENOL_901-10510-2")
      (libsource (lib "eagle-import") (part "AMPHENOL_901-10510-2"))
    )
    (comp (ref "J4")
      (value "BU-1420701851")
      (footprint "eagle-import:BU-1420701851")
      (libsource (lib "eagle-import") (part "BU-1420701851"))
    )
    (comp (ref "J5")
      (value "BU-1420701851")
      (footprint "eagle-import:BU-1420701851")
      (libsource (lib "eagle-import") (part "BU-1420701851"))
    )
    (comp (ref "J6")
      (value "BU-1420701851")
      (footprint "eagle-import:BU-1420701851")
      (libsource (lib "eagle-import") (part "BU-1420701851"))
    )
    (comp (ref "R23")
      (value "R-EU_R0402")
      (footprint "eagle-import:R0402")
      (libsource (lib "eagle-import") (part "R-EU_R0402"))
    )
    (comp (ref "R24")
      (value "R-EU_R0402")
      (footprint "eagle-import:R0402")
      (libsource (lib "eagle-import") (part "R-EU_R0402"))
    )
    (comp (ref "C51")
      (value "100n")
      (footprint "eagle-import:C0402")
      (libsource (lib "eagle-import") (part "C-EU?{colon}2C0402"))
    )
    (comp (ref "C52")
      (value "100n")
      (footprint "eagle-import:C0402")
      (libsource (lib "eagle-import") (part "C-EU?{colon}2C0402"))
    )
    (comp (ref "C53")
      (value "100n")
      (footprint "eagle-import:C0402")
      (libsource (lib "eagle-import") (part "C-EU?{colon}2C0402"))
    )
    (comp (ref "C54")
      (value "100n")
      (footprint "eagle-import:C0402")
      (libsource (lib "eagle-import") (part "C-EU?{colon}2C0402"))
    )
    (comp (ref "C55")
      (value "100n")
      (footprint "eagle-import:C0402")
      (libsource (lib "eagle-import") (part "C-EU?{colon}2C0402"))
    )
    (comp (ref "C56")
      (value "100n")
      (footprint "eagle-import:C0402")
      (libsource (lib "eagle-import") (part "C-EU?{colon}2C0402"))
    )
    (comp (ref "C57")
      (value "100n")
      (footprint "eagle-import:C0402")
      (libsource (lib "eagle-import") (part "C-EU?{colon}2C0402"))
    )
    (comp (ref "C58")
      (value "100n")
      (footprint "eagle-import:C0402")
      (libsource (lib "eagle-import") (part "C-EU?{colon}2C0402"))
    )
    (comp (ref "C59")
      (value "4p")
      (footprint "eagle-import:C0402")
      (libsource (lib "eagle-import") (part "C-EU?{colon}2C0402"))
    )
    (comp (ref "C60")
      (value "4p")
      (footprint "eagle-import:C0402")
      (libsource (lib "eagle-import") (part "C-EU?{colon}2C0402"))
    )
    (comp (ref "C61")
      (value "100n")
      (footprint "eagle-import:C0402")
      (libsource (lib "eagle-import") (part "C-EU?{colon}2C0402"))
    )
    (comp (ref "C62")
      (value "1u")
      (footprint "eagle-import:C0402")
      (libsource (lib "eagle-import") (part "C-EU?{colon}2C0402"))
    )
    (comp (ref "C63")
      (value "1u")
      (footprint "eagle-import:C0402")
      (libsource (lib "eagle-import") (part "C-EU?{colon}2C0402"))
    )
    (comp (ref "IC4")
      (value "SI5332A-GM1")
      (footprint "eagle-import:QFN50P500X500X100-33T345N")
      (libsource (lib "eagle-import") (part "SI5332A-GM1"))
    )
    (comp (ref "JP2")
      (value "PINHD-1X3")
      (footprint "eagle-import:1X03")
      (libsource (lib "eagle-import") (part "PINHD-1X3"))
    )
    (comp (ref "JP7")
      (value "PINHD-1X3")
      (footprint "eagle-import:1X03")
      (libsource (lib "eagle-import") (part "PINHD-1X3"))
    )
    (comp (ref "JP8")
      (value "PINHD-1X3")
      (footprint "eagle-import:1X03")
      (libsource (lib "eagle-import") (part "PINHD-1X3"))
    )
    (comp (ref "JP11")
      (value "PINHD-1X3")
      (footprint "eagle-import:1X03")
      (libsource (lib "eagle-import") (part "PINHD-1X3"))
    )
    (comp (ref "L9")
      (value "FERRITE")
      (footprint "eagle-import:R0402")
      (libsource (lib "eagle-import") (part "FERRITE"))
    )
    (comp (ref "L10")
      (value "FERRITE")
      (footprint "eagle-import:R0402")
      (libsource (lib "eagle-import") (part "FERRITE"))
    )
    (comp (ref "Q1")
      (value "FA-128 26MHz")
      (footprint "eagle-import:FA-128")
      (libsource (lib "eagle-import") (part "FA-128"))
    )
    (comp (ref "R25")
      (value "49R9")
      (footprint "eagle-import:R0402")
      (libsource (lib "eagle-import") (part "R-EU_R0402"))
    )
    (comp (ref "X7")
      (value "SMA_CONNECTOR")
      (footprint "eagle-import:J502-ND-142-0711-821_826")
      (libsource (lib "eagle-import") (part "SMA_CONNECTOR"))
    )
    (comp (ref "X8")
      (value "SMA_CONNECTOR")
      (footprint "eagle-import:J502-ND-142-0711-821_826")
      (libsource (lib "eagle-import") (part "SMA_CONNECTOR"))
    )
    (comp (ref "X9")
      (value "SMA_CONNECTOR")
      (footprint "eagle-import:J502-ND-142-0711-821_826")
      (libsource (lib "eagle-import") (part "SMA_CONNECTOR"))
    )
  )
  (nets
    (net (code "1") (name "+3V3") (class "Default")
      (node (ref "C61") (pin "1") (pinfunction "1_1") (pintype "passive"))
      (node (ref "C63") (pin "1") (pinfunction "1_1") (pintype "passive"))
      (node (ref "C64") (pin "1") (pinfunction "1_1") (pintype "passive"))
      (node (ref "C65") (pin "1") (pinfunction "1_1") (pintype "passive"))
      (node (ref "C66") (pin "1") (pinfunction "1_1") (pintype "passive"))
      (node (ref "C67") (pin "1") (pinfunction "1_1") (pintype "passive"))
      (node (ref "C82") (pin "1") (pinfunction "1_1") (pintype "passive"))
      (node (ref "IC19") (pin "2") (pinfunction "VOUT_2") (pintype "power_in"))
      (node (ref "IC19") (pin "4") (pinfunction "VOUT_4") (pintype "power_in"))
      (node (ref "IC4") (pin "1") (pinfunction "VDD_DIG_1") (pintype "power_in"))
      (node (ref "IC4") (pin "4") (pinfunction "VDD_XTAL_4") (pintype "power_in"))
      (node (ref "IC5") (pin "1") (pinfunction "VBAT_1") (pintype "power_in"))
      (node (ref "IC5") (pin "24") (pinfunction "VDD_24") (pintype "power_in"))
      (node (ref "IC5") (pin "36") (pinfunction "VDDUSB_36") (pintype "bidirectional"))
      (node (ref "IC5") (pin "48") (pinfunction "VDD_48") (pintype "power_in"))
      (node (ref "IC5") (pin "9") (pinfunction "VDDA/VREF+_9") (pintype "power_in"))
      (node (ref "JP9") (pin "1") (pinfunction "1_1") (pintype "passive"))
      (node (ref "L10") (pin "2") (pinfunction "2_2") (pintype "passive"))
      (node (ref "L11") (pin "2") (pinfunction "2_2") (pintype "passive"))
      (node (ref "L9") (pin "1") (pinfunction "1_1") (pintype "passive"))
      (node (ref "R26") (pin "2") (pinfunction "2_2") (pintype "passive"))
      (node (ref "R47") (pin "2") (pinfunction "2_2") (pintype "passive"))
      (node (ref "R48") (pin "2") (pinfunction "2_2") (pintype "passive"))
      (node (ref "R51") (pin "1") (pinfunction "1_1") (pintype "passive"))
    )
    (net (code "2") (name "+5V") (class "Default")
      (node (ref "C78") (pin "1") (pinfunction "1_1") (pintype "passive"))
      (node (ref "IC19") (pin "3") (pinfunction "VIN_3") (pintype "power_in"))
      (node (ref "JP1") (pin "1") (pinfunction "1_1") (pintype "passive"))
      (node (ref "JP12") (pin "2") (pinfunction "2_2") (pintype "passive"))
    )
    (net (code "3") (name "AD9913_CS") (class "Default")
      (node (ref "IC5") (pin "25") (pinfunction "PB12_25") (pintype "bidirectional"))
      (node (ref "JP3") (pin "4") (pinfunction "4_4") (pintype "passive"))
      (node (ref "R34") (pin "1") (pinfunction "1_1") (pintype "passive"))
    )
    (net (code "4") (name "AD9913_IOUT_P") (class "Default")
      (node (ref "C46") (pin "1") (pinfunction "1_1") (pintype "passive"))
      (node (ref "IC2") (pin "20") (pinfunction "IOUT_20") (pintype "output"))
      (node (ref "L3") (pin "1") (pinfunction "1_1") (pintype "passive"))
      (node (ref "R31") (pin "2") (pinfunction "2_2") (pintype "passive"))
    )
    (net (code "5") (name "AD9913_IO_UPDATE") (class "Default")
      (node (ref "IC5") (pin "22") (pinfunction "PB11_22") (pintype "bidirectional"))
      (node (ref "JP3") (pin "5") (pinfunction "5_5") (pintype "passive"))
      (node (ref "R39") (pin "1") (pinfunction "1_1") (pintype "passive"))
    )
    (net (code "6") (name "AD9913_MRESET") (class "Default")
      (node (ref "IC5") (pin "20") (pinfunction "PB2_20") (pintype "bidirectional"))
      (node (ref "JP3") (pin "7") (pinfunction "7_7") (pintype "passive"))
      (node (ref "R37") (pin "1") (pinfunction "1_1") (pintype "passive"))
    )
    (net (code "7") (name "AD9913_OUT_N") (class "Default")
      (node (ref "B1") (pin "3") (pinfunction "SEC_DOT_3") (pintype "bidirectional"))
      (node (ref "C49") (pin "2") (pinfunction "2_2") (pintype "passive"))
      (node (ref "JP5") (pin "1") (pinfunction "1_1") (pintype "passive"))
      (node (ref "L7") (pin "1") (pinfunction "1_1") (pintype "passive"))
    )
    (net (code "8") (name "AD9913_OUT_P") (class "Default")
      (node (ref "B1") (pin "1") (pinfunction "SEC_1") (pintype "bidirectional"))
      (node (ref "C49") (pin "1") (pinfunction "1_1") (pintype "passive"))
      (node (ref "JP5") (pin "2") (pinfunction "2_2") (pintype "passive"))
      (node (ref "L5") (pin "2") (pinfunction "2_2") (pintype "passive"))
    )
    (net (code "9") (name "AD9913_PWR_DWN") (class "Default")
      (node (ref "IC5") (pin "21") (pinfunction "PB10_21") (pintype "bidirectional"))
      (node (ref "JP3") (pin "6") (pinfunction "6_6") (pintype "passive"))
      (node (ref "R38") (pin "1") (pinfunction "1_1") (pintype "passive"))
    )
    (net (code "10") (name "AD9913_REF_LVDS_N") (class "Default")
      (node (ref "IC4") (pin "21") (pinfunction "OUT3B_21") (pintype "output"))
      (node (ref "JP6") (pin "1") (pinfunction "1_1") (pintype "passive"))
    )
    (net (code "11") (name "AD9913_REF_LVDS_P") (class "Default")
      (node (ref "IC4") (pin "22") (pinfunction "OUT3_22") (pintype "output"))
      (node (ref "JP6") (pin "2") (pinfunction "2_2") (pintype "passive"))
    )
    (net (code "12") (name "AD9913_REF_N") (class "Default")
      (node (ref "C45") (pin "2") (pinfunction "2_2") (pintype "passive"))
      (node (ref "IC2") (pin "14") (pinfunction "/REF_CLK_14") (pintype "input"))
    )
    (net (code "13") (name "AD9913_REF_P") (class "Default")
      (node (ref "C44") (pin "2") (pinfunction "2_2") (pintype "passive"))
      (node (ref "IC2") (pin "13") (pinfunction "REF_CLK_13") (pintype "input"))
    )
    (net (code "14") (name "AD9913_SCLK") (class "Default")
      (node (ref "IC5") (pin "26") (pinfunction "PB13_26") (pintype "bidirectional"))
      (node (ref "JP3") (pin "2") (pinfunction "2_2") (pintype "passive"))
      (node (ref "R35") (pin "1") (pinfunction "1_1") (pintype "passive"))
    )
    (net (code "15") (name "AD9913_SDIO") (class "Default")
      (node (ref "IC5") (pin "27") (pinfunction "PB14_27") (pintype "bidirectional"))
      (node (ref "IC5") (pin "28") (pinfunction "PB15_28") (pintype "bidirectional"))
      (node (ref "JP3") (pin "3") (pinfunction "3_3") (pintype "passive"))
      (node (ref "R36") (pin "1") (pinfunction "1_1") (pintype "passive"))
      (node (ref "R46") (pin "1") (pinfunction "1_1") (pintype "passive"))
    )
    (net (code "16") (name "GND") (class "Default")
      (node (ref "B1") (pin "4") (pinfunction "PRI_DOT_4") (pintype "bidirectional"))
      (node (ref "C1") (pin "2") (pinfunction "2_2") (pintype "passive"))
      (node (ref "C10") (pin "2") (pinfunction "2_2") (pintype "passive"))
      (node (ref "C11") (pin "2") (pinfunction "2_2") (pintype "passive"))
      (node (ref "C12") (pin "2") (pinfunction "2_2") (pintype "passive"))
      (node (ref "C13") (pin "2") (pinfunction "2_2") (pintype "passive"))
      (node (ref "C14") (pin "2") (pinfunction "2_2") (pintype "passive"))
      (node (ref "C15") (pin "2") (pinfunction "2_2") (pintype "passive"))
      (node (ref "C16") (pin "2") (pinfunction "2_2") (pintype "passive"))
      (node (ref "C17") (pin "2") (pinfunction "2_2") (pintype "passive"))
      (node (ref "C18") (pin "2") (pinfunction "2_2") (pintype "passive"))
      (node (ref "C195") (pin "2") (pinfunction "2_2") (pintype "passive"))
      (node (ref "C198") (pin "2") (pinfunction "2_2") (pintype "passive"))
      (node (ref "C2") (pin "2") (pinfunction "2_2") (pintype "passive"))
      (node (ref "C20") (pin "2") (pinfunction "2_2") (pintype "passive"))
      (node (ref "C25") (pin "2") (pinfunction "2_2") (pintype "passive"))
      (node (ref "C26") (pin "2") (pinfunction "2_2") (pintype "passive"))
      (node (ref "C27") (pin "2") (pinfunction "2_2") (pintype "passive"))
      (node (ref "C28") (pin "2") (pinfunction "2_2") (pintype "passive"))
      (node (ref "C28") (pin "4") (pinfunction "2_4") (pintype "passive"))
      (node (ref "C29") (pin "2") (pinfunction "2_2") (pintype "passive"))
      (node (ref "C29") (pin "4") (pinfunction "2_4") (pintype "passive"))
      (node (ref "C30") (pin "2") (pinfunction "2_2") (pintype "passive"))
      (node (ref "C30") (pin "4") (pinfunction "2_4") (pintype "passive"))
      (node (ref "C31") (pin "2") (pinfunction "2_2") (pintype "passive"))
      (node (ref "C31") (pin "4") (pinfunction "2_4") (pintype "passive"))
      (node (ref "C32") (pin "2") (pinfunction "2_2") (pintype "passive"))
      (node (ref "C32") (pin "4") (pinfunction "2_4") (pintype "passive"))
      (node (ref "C33") (pin "2") (pinfunction "2_2") (pintype "passive"))
      (node (ref "C33") (pin "4") (pinfunction "2_4") (pintype "passive"))
      (node (ref "C34") (pin "2") (pinfunction "2_2") (pintype "passive"))
      (node (ref "C34") (pin "4") (pinfunction "2_4") (pintype "passive"))
      (node (ref "C35") (pin "2") (pinfunction "2_2") (pintype "passive"))
      (node (ref "C40") (pin "2") (pinfunction "2_2") (pintype "passive"))
      (node (ref "C41") (pin "2") (pinfunction "2_2") (pintype "passive"))
      (node (ref "C42") (pin "2") (pinfunction "2_2") (pintype "passive"))
      (node (ref "C43") (pin "2") (pinfunction "2_2") (pintype "passive"))
      (node (ref "C5") (pin "2") (pinfunction "2_2") (pintype "passive"))
      (node (ref "C51") (pin "2") (pinfunction "2_2") (pintype "passive"))
      (node (ref "C52") (pin "2") (pinfunction "2_2") (pintype "passive"))
      (node (ref "C53") (pin "2") (pinfunction "2_2") (pintype "passive"))
      (node (ref "C54") (pin "2") (pinfunction "2_2") (pintype "passive"))
      (node (ref "C55") (pin "2") (pinfunction "2_2") (pintype "passive"))
      (node (ref "C56") (pin "2") (pinfunction "2_2") (pintype "passive"))
      (node (ref "C57") (pin "2") (pinfunction "2_2") (pintype "passive"))
      (node (ref "C59") (pin "2") (pinfunction "2_2") (pintype "passive"))
      (node (ref "C6") (pin "2") (pinfunction "2_2") (pintype "passive"))
      (node (ref "C60") (pin "2") (pinfunction "2_2") (pintype "passive"))
      (node (ref "C61") (pin "2") (pinfunction "2_2") (pintype "passive"))
      (node (ref "C62") (pin "2") (pinfunction "2_2") (pintype "passive"))
      (node (ref "C63") (pin "2") (pinfunction "2_2") (pintype "passive"))
      (node (ref "C64") (pin "2") (pinfunction "2_2") (pintype "passive"))
      (node (ref "C65") (pin "2") (pinfunction "2_2") (pintype "passive"))
      (node (ref "C66") (pin "2") (pinfunction "2_2") (pintype "passive"))
      (node (ref "C67") (pin "2") (pinfunction "2_2") (pintype "passive"))
      (node (ref "C68") (pin "2") (pinfunction "2_2") (pintype "passive"))
      (node (ref "C7") (pin "2") (pinfunction "2_2") (pintype "passive"))
      (node (ref "C78") (pin "2") (pinfunction "2_2") (pintype "passive"))
      (node (ref "C8") (pin "2") (pinfunction "2_2") (pintype "passive"))
      (node (ref "C82") (pin "2") (pinfunction "2_2") (pintype "passive"))
      (node (ref "C9") (pin "2") (pinfunction "2_2") (pintype "passive"))
      (node (ref "IC1") (pin "12") (pinfunction "EXTVCO_INP_12") (pintype "input"))
      (node (ref "IC1") (pin "13") (pinfunction "EXTVCO_INN_13") (pintype "input"))
      (node (ref "IC1") (pin "35") (pinfunction "TEST_SE_35") (pintype "input"))
      (node (ref "IC1") (pin "37") (pinfunction "GND_37") (pintype "power_in"))
      (node (ref "IC19") (pin "1") (pinfunction "GND_1") (pintype "power_in"))
      (node (ref "IC2") (pin "1") (pinfunction "PS2/ADR5/D5_1") (pintype "bidirectional"))
      (node (ref "IC2") (pin "10") (pinfunction "#SER/PAR_10") (pintype "input"))
      (node (ref "IC2") (pin "11") (pinfunction "AGND_11") (pintype "power_in"))
      (node (ref "IC2") (pin "15") (pinfunction "AGND_15") (pintype "power_in"))
      (node (ref "IC2") (pin "18") (pinfunction "AGND_18") (pintype "power_in"))
      (node (ref "IC2") (pin "2") (pinfunction "PS1/ADR4/D4_2") (pintype "bidirectional"))
      (node (ref "IC2") (pin "21") (pinfunction "AGND_21") (pintype "power_in"))
      (node (ref "IC2") (pin "23") (pinfunction "AGND_23") (pintype "power_in"))
      (node (ref "IC2") (pin "3") (pinfunction "PS0/ADR3/D3_3") (pintype "bidirectional"))
      (node (ref "IC2") (pin "31") (pinfunction "ADR7/D7_31") (pintype "bidirectional"))
      (node (ref "IC2") (pin "32") (pinfunction "ADR6/D6_32") (pintype "bidirectional"))
      (node (ref "IC2") (pin "33") (pinfunction "EP_33") (pintype "power_in"))
      (node (ref "IC2") (pin "5") (pinfunction "DGND_5") (pintype "power_in"))
      (node (ref "IC2") (pin "6") (pinfunction "ADR2/D2_6") (pintype "bidirectional"))
      (node (ref "IC2") (pin "7") (pinfunction "ADR1/D1_7") (pintype "bidirectional"))
      (node (ref "IC2") (pin "8") (pinfunction "ADR0/D0_8") (pintype "bidirectional"))
      (node (ref "IC3") (pin "2") (pinfunction "GND_2") (pintype "power_in"))
      (node (ref "IC34") (pin "2") (pinfunction "GND_2") (pintype "power_in"))
      (node (ref "IC4") (pin "33") (pinfunction "GND_33") (pintype "bidirectional"))
      (node (ref "IC5") (pin "23") (pinfunction "VSS_23") (pintype "power_in"))
      (node (ref "IC5") (pin "35") (pinfunction "VSS_35") (pintype "power_in"))
      (node (ref "IC5") (pin "44") (pinfunction "PH3-BOOT0_44") (pintype "bidirectional"))
      (node (ref "IC5") (pin "47") (pinfunction "VSS_47") (pintype "power_in"))
      (node (ref "IC5") (pin "49") (pinfunction "EP_49") (pintype "bidirectional"))
      (node (ref "IC5") (pin "8") (pinfunction "VSSA/VREF-_8") (pintype "power_in"))
      (node (ref "J1") (pin "G1") (pinfunction "2_G1") (pintype "passive"))
      (node (ref "J1") (pin "G2") (pinfunction "2_G2") (pintype "passive"))
      (node (ref "J1") (pin "G3") (pinfunction "2_G3") (pintype "passive"))
      (node (ref "J1") (pin "G4") (pinfunction "2_G4") (pintype "passive"))
      (node (ref "J2") (pin "G1") (pinfunction "2_G1") (pintype "passive"))
      (node (ref "J2") (pin "G2") (pinfunction "2_G2") (pintype "passive"))
      (node (ref "J2") (pin "G3") (pinfunction "2_G3") (pintype "passive"))
      (node (ref "J2") (pin "G4") (pinfunction "2_G4") (pintype "passive"))
      (node (ref "J3") (pin "G1") (pinfunction "2_G1") (pintype "passive"))
      (node (ref "J3") (pin "G2") (pinfunction "2_G2") (pintype "passive"))
      (node (ref "J3") (pin "G3") (pinfunction "2_G3") (pintype "passive"))
      (node (ref "J3") (pin "G4") (pinfunction "2_G4") (pintype "passive"))
      (node (ref "J4") (pin "G@1") (pinfunction "2_G@1") (pintype "passive"))
      (node (ref "J4") (pin "G@2") (pinfunction "2_G@2") (pintype "passive"))
      (node (ref "J4") (pin "G@3") (pinfunction "2_G@3") (pintype "passive"))
      (node (ref "J4") (pin "G@4") (pinfunction "2_G@4") (pintype "passive"))
      (node (ref "J5") (pin "G@1") (pinfunction "2_G@1") (pintype "passive"))
      (node (ref "J5") (pin "G@2") (pinfunction "2_G@2") (pintype "passive"))
      (node (ref "J5") (pin "G@3") (pinfunction "2_G@3") (pintype "passive"))
      (node (ref "J5") (pin "G@4") (pinfunction "2_G@4") (pintype "passive"))
      (node (ref "J6") (pin "G@1") (pinfunction "2_G@1") (pintype "passive"))
      (node (ref "J6") (pin "G@2") (pinfunction "2_G@2") (pintype "passive"))
      (node (ref "J6") (pin "G@3") (pinfunction "2_G@3") (pintype "passive"))
      (node (ref "J6") (pin "G@4") (pinfunction "2_G@4") (pintype "passive"))
      (node (ref "JP1") (pin "3") (pinfunction "3_3") (pintype "passive"))
      (node (ref "JP10") (pin "2") (pinfunction "2_2") (pintype "passive"))
      (node (ref "JP11") (pin "3") (pinfunction "3_3") (pintype "passive"))
      (node (ref "JP12") (pin "3") (pinfunction "3_3") (pintype "passive"))
      (node (ref "JP2") (pin "2") (pinfunction "2_2") (pintype "passive"))
      (node (ref "JP3") (pin "1") (pinfunction "1_1") (pintype "passive"))
      (node (ref "JP3") (pin "8") (pinfunction "8_8") (pintype "passive"))
      (node (ref "JP4") (pin "1") (pinfunction "1_1") (pintype "passive"))
      (node (ref "JP4") (pin "8") (pinfunction "8_8") (pintype "passive"))
      (node (ref "JP5") (pin "5") (pinfunction "5_5") (pintype "passive"))
      (node (ref "JP6") (pin "5") (pinfunction "5_5") (pintype "passive"))
      (node (ref "JP7") (pin "2") (pinfunction "2_2") (pintype "passive"))
      (node (ref "JP8") (pin "2") (pinfunction "2_2") (pintype "passive"))
      (node (ref "JP9") (pin "3") (pinfunction "3_3") (pintype "passive"))
      (node (ref "Q1") (pin "2") (pinfunction "2_2") (pintype "passive"))
      (node (ref "Q1") (pin "4") (pinfunction "4_4") (pintype "passive"))
      (node (ref "R23") (pin "1") (pinfunction "1_1") (pintype "passive"))
      (node (ref "R24") (pin "1") (pinfunction "1_1") (pintype "passive"))
      (node (ref "R25") (pin "1") (pinfunction "1_1") (pintype "passive"))
      (node (ref "R27") (pin "2") (pinfunction "2_2") (pintype "passive"))
      (node (ref "R28") (pin "2") (pinfunction "2_2") (pintype "passive"))
      (node (ref "R29") (pin "1") (pinfunction "1_1") (pintype "passive"))
      (node (ref "R30") (pin "1") (pinfunction "1_1") (pintype "passive"))
      (node (ref "R31") (pin "1") (pinfunction "1_1") (pintype "passive"))
      (node (ref "R33") (pin "1") (pinfunction "1_1") (pintype "passive"))
      (node (ref "R40") (pin "1") (pinfunction "1_1") (pintype "passive"))
      (node (ref "R41") (pin "1") (pinfunction "1_1") (pintype "passive"))
      (node (ref "R42") (pin "1") (pinfunction "1_1") (pintype "passive"))
      (node (ref "R43") (pin "1") (pinfunction "1_1") (pintype "passive"))
      (node (ref "R44") (pin "1") (pinfunction "1_1") (pintype "passive"))
      (node (ref "R45") (pin "1") (pinfunction "1_1") (pintype "passive"))
      (node (ref "R6") (pin "1") (pinfunction "1_1") (pintype "passive"))
      (node (ref "SH1") (pin "1") (pinfunction "GND_1") (pintype "bidirectional"))
      (node (ref "SH1") (pin "10") (pinfunction "GND_10") (pintype "bidirectional"))
      (node (ref "SH1") (pin "11") (pinfunction "GND_11") (pintype "bidirectional"))
      (node (ref "SH1") (pin "12") (pinfunction "GND_12") (pintype "bidirectional"))
      (node (ref "SH1") (pin "13") (pinfunction "GND_13") (pintype "bidirectional"))
      (node (ref "SH1") (pin "14") (pinfunction "GND_14") (pintype "bidirectional"))
      (node (ref "SH1") (pin "15") (pinfunction "GND_15") (pintype "bidirectional"))
      (node (ref "SH1") (pin "16") (pinfunction "GND_16") (pintype "bidirectional"))
      (node (ref "SH1") (pin "17") (pinfunction "GND_17") (pintype "bidirectional"))
      (node (ref "SH1") (pin "18") (pinfunction "GND_18") (pintype "bidirectional"))
      (node (ref "SH1") (pin "19") (pinfunction "GND_19") (pintype "bidirectional"))
      (node (ref "SH1") (pin "2") (pinfunction "GND_2") (pintype "bidirectional"))
      (node (ref "SH1") (pin "20") (pinfunction "GND_20") (pintype "bidirectional"))
      (node (ref "SH1") (pin "3") (pinfunction "GND_3") (pintype "bidirectional"))
      (node (ref "SH1") (pin "4") (pinfunction "GND_4") (pintype "bidirectional"))
      (node (ref "SH1") (pin "5") (pinfunction "GND_5") (pintype "bidirectional"))
      (node (ref "SH1") (pin "6") (pinfunction "GND_6") (pintype "bidirectional"))
      (node (ref "SH1") (pin "7") (pinfunction "GND_7") (pintype "bidirectional"))
      (node (ref "SH1") (pin "8") (pinfunction "GND_8") (pintype "bidirectional"))
      (node (ref "SH1") (pin "9") (pinfunction "GND_9") (pintype "bidirectional"))
      (node (ref "SJ1") (pin "1") (pinfunction "1_1") (pintype "passive"))
      (node (ref "T1") (pin "2") (pinfunction "IN-_2") (pintype "bidirectional"))
      (node (ref "X1") (pin "G@1") (pinfunction "2_G@1") (pintype "passive"))
      (node (ref "X1") (pin "G@2") (pinfunction "2_G@2") (pintype "passive"))
      (node (ref "X1") (pin "G@3") (pinfunction "2_G@3") (pintype "passive"))
      (node (ref "X1") (pin "G@4") (pinfunction "2_G@4") (pintype "passive"))
      (node (ref "X10") (pin "5") (pinfunction "5_5") (pintype "passive"))
      (node (ref "X10") (pin "M1") (pinfunction "S1_M1") (pintype "passive"))
      (node (ref "X10") (pin "M2") (pinfunction "S2_M2") (pintype "passive"))
      (node (ref "X10") (pin "M3") (pinfunction "S3_M3") (pintype "passive"))
      (node (ref "X10") (pin "M4") (pinfunction "S4_M4") (pintype "passive"))
      (node (ref "X2") (pin "G@1") (pinfunction "2_G@1") (pintype "passive"))
      (node (ref "X2") (pin "G@2") (pinfunction "2_G@2") (pintype "passive"))
      (node (ref "X2") (pin "G@3") (pinfunction "2_G@3") (pintype "passive"))
      (node (ref "X2") (pin "G@4") (pinfunction "2_G@4") (pintype "passive"))
      (node (ref "X3") (pin "G@1") (pinfunction "2_G@1") (pintype "passive"))
      (node (ref "X3") (pin "G@2") (pinfunction "2_G@2") (pintype "passive"))
      (node (ref "X3") (pin "G@3") (pinfunction "2_G@3") (pintype "passive"))
      (node (ref "X3") (pin "G@4") (pinfunction "2_G@4") (pintype "passive"))
      (node (ref "X4") (pin "G@1") (pinfunction "2_G@1") (pintype "passive"))
      (node (ref "X4") (pin "G@2") (pinfunction "2_G@2") (pintype "passive"))
      (node (ref "X4") (pin "G@3") (pinfunction "2_G@3") (pintype "passive"))
      (node (ref "X4") (pin "G@4") (pinfunction "2_G@4") (pintype "passive"))
      (node (ref "X5") (pin "G@1") (pinfunction "2_G@1") (pintype "passive"))
      (node (ref "X5") (pin "G@2") (pinfunction "2_G@2") (pintype "passive"))
      (node (ref "X5") (pin "G@3") (pinfunction "2_G@3") (pintype "passive"))
      (node (ref "X5") (pin "G@4") (pinfunction "2_G@4") (pintype "passive"))
      (node (ref "X6") (pin "G@1") (pinfunction "2_G@1") (pintype "passive"))
      (node (ref "X6") (pin "G@2") (pinfunction "2_G@2") (pintype "passive"))
      (node (ref "X6") (pin "G@3") (pinfunction "2_G@3") (pintype "passive"))
      (node (ref "X6") (pin "G@4") (pinfunction "2_G@4") (pintype "passive"))
      (node (ref "X7") (pin "G@1") (pinfunction "2_G@1") (pintype "passive"))
      (node (ref "X7") (pin "G@2") (pinfunction "2_G@2") (pintype "passive"))
      (node (ref "X7") (pin "G@3") (pinfunction "2_G@3") (pintype "passive"))
      (node (ref "X7") (pin "G@4") (pinfunction "2_G@4") (pintype "passive"))
      (node (ref "X8") (pin "G@1") (pinfunction "2_G@1") (pintype "passive"))
      (node (ref "X8") (pin "G@2") (pinfunction "2_G@2") (pintype "passive"))
      (node (ref "X8") (pin "G@3") (pinfunction "2_G@3") (pintype "passive"))
      (node (ref "X8") (pin "G@4") (pinfunction "2_G@4") (pintype "passive"))
      (node (ref "X9") (pin "G@1") (pinfunction "2_G@1") (pintype "passive"))
      (node (ref "X9") (pin "G@2") (pinfunction "2_G@2") (pintype "passive"))
      (node (ref "X9") (pin "G@3") (pinfunction "2_G@3") (pintype "passive"))
      (node (ref "X9") (pin "G@4") (pinfunction "2_G@4") (pintype "passive"))
    )
    (net (code "17") (name "Net-(B1-PRI)") (class "Default")
      (node (ref "B1") (pin "5") (pinfunction "PRI_5") (pintype "bidirectional"))
      (node (ref "C50") (pin "1") (pinfunction "1_1") (pintype "passive"))
    )
    (net (code "18") (name "Net-(B1-SEC_CT)") (class "Default")
      (node (ref "B1") (pin "2") (pinfunction "SEC_CT_2") (pintype "bidirectional"))
      (node (ref "SJ1") (pin "2") (pinfunction "2_2") (pintype "passive"))
    )
    (net (code "19") (name "Net-(C7-Pad1)") (class "Default")
      (node (ref "C7") (pin "1") (pinfunction "1_1") (pintype "passive"))
      (node (ref "R2") (pin "2") (pinfunction "2_2") (pintype "passive"))
    )
    (net (code "20") (name "Net-(C19-Pad2)") (class "Default")
      (node (ref "C19") (pin "2") (pinfunction "2_2") (pintype "passive"))
      (node (ref "R6") (pin "2") (pinfunction "2_2") (pintype "passive"))
      (node (ref "R7") (pin "2") (pinfunction "2_2") (pintype "passive"))
    )
    (net (code "21") (name "Net-(C21-Pad2)") (class "Default")
      (node (ref "C21") (pin "2") (pinfunction "2_2") (pintype "passive"))
      (node (ref "R21") (pin "2") (pinfunction "2_2") (pintype "passive"))
      (node (ref "R27") (pin "1") (pinfunction "1_1") (pintype "passive"))
    )
    (net (code "22") (name "Net-(C22-Pad2)") (class "Default")
      (node (ref "C22") (pin "2") (pinfunction "2_2") (pintype "passive"))
      (node (ref "R22") (pin "2") (pinfunction "2_2") (pintype "passive"))
      (node (ref "R28") (pin "1") (pinfunction "1_1") (pintype "passive"))
    )
    (net (code "23") (name "Net-(C28-Pad1)") (class "Default")
      (node (ref "C28") (pin "1") (pinfunction "1_1") (pintype "passive"))
      (node (ref "R10") (pin "1") (pinfunction "1_1") (pintype "passive"))
    )
    (net (code "24") (name "Net-(C28-Pad3)") (class "Default")
      (node (ref "C28") (pin "3") (pinfunction "3_3") (pintype "passive"))
      (node (ref "R9") (pin "2") (pinfunction "2_2") (pintype "passive"))
    )
    (net (code "25") (name "Net-(C29-Pad1)") (class "Default")
      (node (ref "C29") (pin "1") (pinfunction "1_1") (pintype "passive"))
      (node (ref "R12") (pin "1") (pinfunction "1_1") (pintype "passive"))
    )
    (net (code "26") (name "Net-(C29-Pad3)") (class "Default")
      (node (ref "C29") (pin "3") (pinfunction "3_3") (pintype "passive"))
      (node (ref "R11") (pin "2") (pinfunction "2_2") (pintype "passive"))
    )
    (net (code "27") (name "Net-(C30-Pad1)") (class "Default")
      (node (ref "C30") (pin "1") (pinfunction "1_1") (pintype "passive"))
      (node (ref "R14") (pin "1") (pinfunction "1_1") (pintype "passive"))
    )
    (net (code "28") (name "Net-(C30-Pad3)") (class "Default")
      (node (ref "C30") (pin "3") (pinfunction "3_3") (pintype "passive"))
      (node (ref "R13") (pin "2") (pinfunction "2_2") (pintype "passive"))
    )
    (net (code "29") (name "Net-(C31-Pad1)") (class "Default")
      (node (ref "C31") (pin "1") (pinfunction "1_1") (pintype "passive"))
      (node (ref "R16") (pin "1") (pinfunction "1_1") (pintype "passive"))
    )
    (net (code "30") (name "Net-(C31-Pad3)") (class "Default")
      (node (ref "C31") (pin "3") (pinfunction "3_3") (pintype "passive"))
      (node (ref "R15") (pin "2") (pinfunction "2_2") (pintype "passive"))
    )
    (net (code "31") (name "Net-(C32-Pad1)") (class "Default")
      (node (ref "C32") (pin "1") (pinfunction "1_1") (pintype "passive"))
      (node (ref "R18") (pin "1") (pinfunction "1_1") (pintype "passive"))
    )
    (net (code "32") (name "Net-(C32-Pad3)") (class "Default")
      (node (ref "C32") (pin "3") (pinfunction "3_3") (pintype "passive"))
      (node (ref "R17") (pin "2") (pinfunction "2_2") (pintype "passive"))
    )
    (net (code "33") (name "Net-(C33-Pad1)") (class "Default")
      (node (ref "C33") (pin "1") (pinfunction "1_1") (pintype "passive"))
      (node (ref "R20") (pin "1") (pinfunction "1_1") (pintype "passive"))
    )
    (net (code "34") (name "Net-(C33-Pad3)") (class "Default")
      (node (ref "C33") (pin "3") (pinfunction "3_3") (pintype "passive"))
      (node (ref "R19") (pin "2") (pinfunction "2_2") (pintype "passive"))
    )
    (net (code "35") (name "Net-(C34-Pad1)") (class "Default")
      (node (ref "C34") (pin "1") (pinfunction "1_1") (pintype "passive"))
      (node (ref "L2") (pin "2") (pinfunction "2_2") (pintype "passive"))
    )
    (net (code "36") (name "Net-(C34-Pad3)") (class "Default")
      (node (ref "C34") (pin "3") (pinfunction "3_3") (pintype "passive"))
      (node (ref "L1") (pin "1") (pinfunction "1_1") (pintype "passive"))
    )
    (net (code "37") (name "Net-(C36-Pad1)") (class "Default")
      (node (ref "C36") (pin "1") (pinfunction "1_1") (pintype "passive"))
      (node (ref "X4") (pin "1") (pinfunction "1_1") (pintype "passive"))
    )
    (net (code "38") (name "Net-(C36-Pad2)") (class "Default")
      (node (ref "C36") (pin "2") (pinfunction "2_2") (pintype "passive"))
      (node (ref "JP6") (pin "6") (pinfunction "6_6") (pintype "passive"))
      (node (ref "R33") (pin "2") (pinfunction "2_2") (pintype "passive"))
    )
    (net (code "39") (name "Net-(C37-Pad1)") (class "Default")
      (node (ref "C37") (pin "1") (pinfunction "1_1") (pintype "passive"))
      (node (ref "JP5") (pin "3") (pinfunction "3_3") (pintype "passive"))
      (node (ref "JP5") (pin "7") (pinfunction "7_7") (pintype "passive"))
    )
    (net (code "40") (name "Net-(C38-Pad2)") (class "Default")
      (node (ref "C38") (pin "2") (pinfunction "2_2") (pintype "passive"))
      (node (ref "JP5") (pin "4") (pinfunction "4_4") (pintype "passive"))
      (node (ref "JP5") (pin "8") (pinfunction "8_8") (pintype "passive"))
    )
    (net (code "41") (name "Net-(C39-Pad2)") (class "Default")
      (node (ref "C39") (pin "2") (pinfunction "2_2") (pintype "passive"))
      (node (ref "X3") (pin "1") (pinfunction "1_1") (pintype "passive"))
    )
    (net (code "42") (name "Net-(C44-Pad1)") (class "Default")
      (node (ref "C44") (pin "1") (pinfunction "1_1") (pintype "passive"))
      (node (ref "JP6") (pin "4") (pinfunction "4_4") (pintype "passive"))
      (node (ref "R32") (pin "2") (pinfunction "2_2") (pintype "passive"))
    )
    (net (code "43") (name "Net-(C45-Pad1)") (class "Default")
      (node (ref "C45") (pin "1") (pinfunction "1_1") (pintype "passive"))
      (node (ref "JP6") (pin "3") (pinfunction "3_3") (pintype "passive"))
      (node (ref "R32") (pin "1") (pinfunction "1_1") (pintype "passive"))
    )
    (net (code "44") (name "Net-(C47-Pad1)") (class "Default")
      (node (ref "C47") (pin "1") (pinfunction "1_1") (pintype "passive"))
      (node (ref "L3") (pin "2") (pinfunction "2_2") (pintype "passive"))
      (node (ref "L4") (pin "1") (pinfunction "1_1") (pintype "passive"))
    )
    (net (code "45") (name "Net-(C47-Pad2)") (class "Default")
      (node (ref "C47") (pin "2") (pinfunction "2_2") (pintype "passive"))
      (node (ref "L6") (pin "1") (pinfunction "1_1") (pintype "passive"))
      (node (ref "L8") (pin "2") (pinfunction "2_2") (pintype "passive"))
    )
    (net (code "46") (name "Net-(C48-Pad1)") (class "Default")
      (node (ref "C48") (pin "1") (pinfunction "1_1") (pintype "passive"))
      (node (ref "L4") (pin "2") (pinfunction "2_2") (pintype "passive"))
      (node (ref "L5") (pin "1") (pinfunction "1_1") (pintype "passive"))
    )
    (net (code "47") (name "Net-(C48-Pad2)") (class "Default")
      (node (ref "C48") (pin "2") (pinfunction "2_2") (pintype "passive"))
      (node (ref "L7") (pin "2") (pinfunction "2_2") (pintype "passive"))
      (node (ref "L8") (pin "1") (pinfunction "1_1") (pintype "passive"))
    )
    (net (code "48") (name "Net-(C50-Pad2)") (class "Default")
      (node (ref "C50") (pin "2") (pinfunction "2_2") (pintype "passive"))
      (node (ref "X6") (pin "1") (pinfunction "1_1") (pintype "passive"))
    )
    (net (code "49") (name "Net-(C58-Pad1)") (class "Default")
      (node (ref "C58") (pin "1") (pinfunction "1_1") (pintype "passive"))
      (node (ref "X7") (pin "1") (pinfunction "1_1") (pintype "passive"))
    )
    (net (code "50") (name "Net-(IC1A-CBYP)") (class "Default")
      (node (ref "C4") (pin "2") (pinfunction "2_2") (pintype "passive"))
      (node (ref "IC1") (pin "7") (pinfunction "CBYP_7") (pintype "passive"))
    )
    (net (code "51") (name "Net-(IC1A-CBYP_4V5)") (class "Default")
      (node (ref "C3") (pin "2") (pinfunction "2_2") (pintype "passive"))
      (node (ref "IC1") (pin "1") (pinfunction "CBYP_4V5_1") (pintype "passive"))
    )
    (net (code "52") (name "Net-(IC1A-VIN_LDO_4V5)") (class "Default")
      (node (ref "C25") (pin "1") (pinfunction "1_1") (pintype "passive"))
      (node (ref "C26") (pin "1") (pinfunction "1_1") (pintype "passive"))
      (node (ref "C27") (pin "1") (pinfunction "1_1") (pintype "passive"))
      (node (ref "C35") (pin "1") (pinfunction "1_1") (pintype "passive"))
      (node (ref "IC1") (pin "18") (pinfunction "VIN_LDO_REF_18") (pintype "power_in"))
      (node (ref "IC1") (pin "28") (pinfunction "VIN_LDO_RF_DIG_28") (pintype "power_in"))
      (node (ref "IC1") (pin "36") (pinfunction "VIN_LDO_4V5_36") (pintype "power_in"))
      (node (ref "IC1") (pin "9") (pinfunction "VIN_LDO_VCO_9") (pintype "power_in"))
      (node (ref "L1") (pin "2") (pinfunction "2_2") (pintype "passive"))
    )
    (net (code "53") (name "Net-(IC1A-VR)") (class "Default")
      (node (ref "C1") (pin "1") (pinfunction "1_1") (pintype "passive"))
      (node (ref "C2") (pin "1") (pinfunction "1_1") (pintype "passive"))
      (node (ref "IC1") (pin "10") (pinfunction "VR_10") (pintype "passive"))
    )
    (net (code "54") (name "Net-(IC1A-VREG_RF)") (class "Default")
      (node (ref "IC1") (pin "29") (pinfunction "VREG_RF_29") (pintype "output"))
      (node (ref "R2") (pin "1") (pinfunction "1_1") (pintype "passive"))
    )
    (net (code "55") (name "Net-(IC1B-HW_PD)") (class "Default")
      (node (ref "IC1") (pin "4") (pinfunction "HW_PD_4") (pintype "input"))
      (node (ref "R17") (pin "1") (pinfunction "1_1") (pintype "passive"))
    )
    (net (code "56") (name "Net-(IC1B-ICP)") (class "Default")
      (node (ref "C18") (pin "1") (pinfunction "1_1") (pintype "passive"))
      (node (ref "C19") (pin "1") (pinfunction "1_1") (pintype "passive"))
      (node (ref "IC1") (pin "15") (pinfunction "ICP_15") (pintype "output"))
      (node (ref "R8") (pin "2") (pinfunction "2_2") (pintype "passive"))
    )
    (net (code "57") (name "Net-(IC1B-LD_SDO)") (class "Default")
      (node (ref "IC1") (pin "22") (pinfunction "LD_SDO_22") (pintype "output"))
      (node (ref "R13") (pin "1") (pinfunction "1_1") (pintype "passive"))
    )
    (net (code "58") (name "Net-(IC1B-LE)") (class "Default")
      (node (ref "IC1") (pin "25") (pinfunction "LE_25") (pintype "input"))
      (node (ref "R15") (pin "1") (pinfunction "1_1") (pintype "passive"))
    )
    (net (code "59") (name "Net-(IC1B-PD_RF1)") (class "Default")
      (node (ref "IC1") (pin "5") (pinfunction "PD_RF1_5") (pintype "input"))
      (node (ref "R19") (pin "1") (pinfunction "1_1") (pintype "passive"))
    )
    (net (code "60") (name "Net-(IC1B-PD_RF2{slash}FL_SW)") (class "Default")
      (node (ref "IC1") (pin "6") (pinfunction "PD_RF2/FL_SW_6") (pintype "open_collector"))
      (node (ref "R7") (pin "1") (pinfunction "1_1") (pintype "passive"))
    )
    (net (code "61") (name "Net-(IC1B-REF_CLKN)") (class "Default")
      (node (ref "C38") (pin "1") (pinfunction "1_1") (pintype "passive"))
      (node (ref "IC1") (pin "20") (pinfunction "REF_CLKN_20") (pintype "input"))
    )
    (net (code "62") (name "Net-(IC1B-REF_CLKP)") (class "Default")
      (node (ref "C37") (pin "2") (pinfunction "2_2") (pintype "passive"))
      (node (ref "IC1") (pin "21") (pinfunction "REF_CLKP_21") (pintype "input"))
    )
    (net (code "63") (name "Net-(IC1B-RF1_OUTN)") (class "Default")
      (node (ref "C22") (pin "1") (pinfunction "1_1") (pintype "passive"))
      (node (ref "IC1") (pin "30") (pinfunction "RF1_OUTN_30") (pintype "bidirectional"))
    )
    (net (code "64") (name "Net-(IC1B-RF1_OUTP)") (class "Default")
      (node (ref "C21") (pin "1") (pinfunction "1_1") (pintype "passive"))
      (node (ref "IC1") (pin "31") (pinfunction "RF1_OUTP_31") (pintype "bidirectional"))
    )
    (net (code "65") (name "Net-(IC1B-RF2_OUTN)") (class "Default")
      (node (ref "C24") (pin "1") (pinfunction "1_1") (pintype "passive"))
      (node (ref "IC1") (pin "33") (pinfunction "RF2_OUTN_33") (pintype "bidirectional"))
    )
    (net (code "66") (name "Net-(IC1B-RF2_OUTP)") (class "Default")
      (node (ref "C23") (pin "1") (pinfunction "1_1") (pintype "passive"))
      (node (ref "IC1") (pin "34") (pinfunction "RF2_OUTP_34") (pintype "bidirectional"))
    )
    (net (code "67") (name "Net-(IC1B-SCK)") (class "Default")
      (node (ref "IC1") (pin "24") (pinfunction "SCK_24") (pintype "input"))
      (node (ref "R9") (pin "1") (pinfunction "1_1") (pintype "passive"))
    )
    (net (code "68") (name "Net-(IC1B-SDI)") (class "Default")
      (node (ref "IC1") (pin "23") (pinfunction "SDI_23") (pintype "input"))
      (node (ref "R11") (pin "1") (pinfunction "1_1") (pintype "passive"))
    )
    (net (code "69") (name "Net-(IC2-DVDD)") (class "Default")
      (node (ref "C17") (pin "1") (pinfunction "1_1") (pintype "passive"))
      (node (ref "C40") (pin "1") (pinfunction "1_1") (pintype "passive"))
      (node (ref "IC2") (pin "4") (pinfunction "DVDD_4") (pintype "power_in"))
      (node (ref "IC3") (pin "5") (pinfunction "VOUT_5") (pintype "power_in"))
    )
    (net (code "70") (name "Net-(IC2-IO_UPDATE)") (class "Default")
      (node (ref "IC2") (pin "27") (pinfunction "IO_UPDATE_27") (pintype "input"))
      (node (ref "R39") (pin "2") (pinfunction "2_2") (pintype "passive"))
      (node (ref "R45") (pin "2") (pinfunction "2_2") (pintype "passive"))
    )
    (net (code "71") (name "Net-(IC2-MASTER_RESET)") (class "Default")
      (node (ref "IC2") (pin "25") (pinfunction "MASTER_RESET_25") (pintype "input"))
      (node (ref "R37") (pin "2") (pinfunction "2_2") (pintype "passive"))
      (node (ref "R43") (pin "2") (pinfunction "2_2") (pintype "passive"))
    )
    (net (code "72") (name "Net-(IC2-PWR_DWN_CTL)") (class "Default")
      (node (ref "IC2") (pin "26") (pinfunction "PWR_DWN_CTL_26") (pintype "input"))
      (node (ref "R38") (pin "2") (pinfunction "2_2") (pintype "passive"))
      (node (ref "R44") (pin "2") (pinfunction "2_2") (pintype "passive"))
    )
    (net (code "73") (name "Net-(IC2-RSET)") (class "Default")
      (node (ref "IC2") (pin "24") (pinfunction "RSET_24") (pintype "input"))
      (node (ref "R29") (pin "2") (pinfunction "2_2") (pintype "passive"))
    )
    (net (code "74") (name "Net-(IC2-SCLK)") (class "Default")
      (node (ref "IC2") (pin "30") (pinfunction "SCLK_30") (pintype "input"))
      (node (ref "R35") (pin "2") (pinfunction "2_2") (pintype "passive"))
      (node (ref "R41") (pin "2") (pinfunction "2_2") (pintype "passive"))
    )
    (net (code "75") (name "Net-(IC2-SDIO)") (class "Default")
      (node (ref "IC2") (pin "29") (pinfunction "SDIO_29") (pintype "bidirectional"))
      (node (ref "R36") (pin "2") (pinfunction "2_2") (pintype "passive"))
      (node (ref "R42") (pin "2") (pinfunction "2_2") (pintype "passive"))
    )
    (net (code "76") (name "Net-(IC2-{slash}CS)") (class "Default")
      (node (ref "IC2") (pin "28") (pinfunction "/CS_28") (pintype "input"))
      (node (ref "R34") (pin "2") (pinfunction "2_2") (pintype "passive"))
      (node (ref "R40") (pin "2") (pinfunction "2_2") (pintype "passive"))
    )
    (net (code "77") (name "Net-(IC2-{slash}IOUT)") (class "Default")
      (node (ref "C46") (pin "2") (pinfunction "2_2") (pintype "passive"))
      (node (ref "IC2") (pin "19") (pinfunction "/IOUT_19") (pintype "output"))
      (node (ref "L6") (pin "2") (pinfunction "2_2") (pintype "passive"))
      (node (ref "R30") (pin "2") (pinfunction "2_2") (pintype "passive"))
    )
    (net (code "78") (name "Net-(IC3-EN)") (class "Default")
      (node (ref "C13") (pin "1") (pinfunction "1_1") (pintype "passive"))
      (node (ref "C195") (pin "1") (pinfunction "1_1") (pintype "passive"))
      (node (ref "IC3") (pin "1") (pinfunction "VIN_1") (pintype "power_in"))
      (node (ref "IC3") (pin "3") (pinfunction "EN_3") (pintype "input"))
      (node (ref "IC34") (pin "1") (pinfunction "VIN_1") (pintype "power_in"))
      (node (ref "IC34") (pin "3") (pinfunction "EN_3") (pintype "input"))
      (node (ref "L11") (pin "1") (pinfunction "1_1") (pintype "passive"))
      (node (ref "R46") (pin "2") (pinfunction "2_2") (pintype "passive"))
    )
    (net (code "79") (name "Net-(IC4-CLKIN_2)") (class "Default")
      (node (ref "C58") (pin "2") (pinfunction "2_2") (pintype "passive"))
      (node (ref "IC4") (pin "2") (pinfunction "CLKIN_2_2") (pintype "input"))
      (node (ref "R25") (pin "2") (pinfunction "2_2") (pintype "passive"))
    )
    (net (code "80") (name "Net-(IC4-CLKIN_2B)") (class "Default")
      (node (ref "C57") (pin "1") (pinfunction "1_1") (pintype "passive"))
      (node (ref "IC4") (pin "3") (pinfunction "CLKIN_2B_3") (pintype "input"))
    )
    (net (code "81") (name "Net-(IC4-VDDA)") (class "Default")
      (node (ref "C62") (pin "1") (pinfunction "1_1") (pintype "passive"))
      (node (ref "IC4") (pin "7") (pinfunction "VDDA_7") (pintype "power_in"))
      (node (ref "L9") (pin "2") (pinfunction "2_2") (pintype "passive"))
    )
    (net (code "82") (name "Net-(IC4-XA{slash}CLKIN1)") (class "Default")
      (node (ref "C59") (pin "1") (pinfunction "1_1") (pintype "passive"))
      (node (ref "IC4") (pin "5") (pinfunction "XA/CLKIN1_5") (pintype "input"))
      (node (ref "Q1") (pin "1") (pinfunction "1_1") (pintype "passive"))
    )
    (net (code "83") (name "Net-(IC4-XB)") (class "Default")
      (node (ref "C60") (pin "1") (pinfunction "1_1") (pintype "passive"))
      (node (ref "IC4") (pin "6") (pinfunction "XB_6") (pintype "input"))
      (node (ref "Q1") (pin "3") (pinfunction "3_3") (pintype "passive"))
    )
    (net (code "84") (name "Net-(IC5-NRST)") (class "Default")
      (node (ref "C68") (pin "1") (pinfunction "1_1") (pintype "passive"))
      (node (ref "IC5") (pin "7") (pinfunction "NRST_7") (pintype "input"))
      (node (ref "JP9") (pin "5") (pinfunction "5_5") (pintype "passive"))
      (node (ref "R26") (pin "1") (pinfunction "1_1") (pintype "passive"))
    )
    (net (code "85") (name "Net-(IC5-PA11)") (class "Default")
      (node (ref "IC5") (pin "32") (pinfunction "PA11_32") (pintype "bidirectional"))
      (node (ref "R49") (pin "1") (pinfunction "1_1") (pintype "passive"))
    )
    (net (code "86") (name "Net-(IC5-PA12)") (class "Default")
      (node (ref "IC5") (pin "33") (pinfunction "PA12_33") (pintype "bidirectional"))
      (node (ref "R50") (pin "2") (pinfunction "2_2") (pintype "passive"))
    )
    (net (code "87") (name "Net-(IC5-PA13{slash}SWDIO)") (class "Default")
      (node (ref "IC5") (pin "34") (pinfunction "PA13/SWDIO_34") (pintype "bidirectional"))
      (node (ref "JP9") (pin "4") (pinfunction "4_4") (pintype "passive"))
    )
    (net (code "88") (name "Net-(IC5-PA14{slash}SWCLK)") (class "Default")
      (node (ref "IC5") (pin "37") (pinfunction "PA14/SWCLK_37") (pintype "bidirectional"))
      (node (ref "JP9") (pin "2") (pinfunction "2_2") (pintype "passive"))
    )
    (net (code "89") (name "Net-(IC34-VOUT)") (class "Default")
      (node (ref "C198") (pin "1") (pinfunction "1_1") (pintype "passive"))
      (node (ref "C41") (pin "1") (pinfunction "1_1") (pintype "passive"))
      (node (ref "C42") (pin "1") (pinfunction "1_1") (pintype "passive"))
      (node (ref "C43") (pin "1") (pinfunction "1_1") (pintype "passive"))
      (node (ref "IC2") (pin "12") (pinfunction "AVDD_12") (pintype "power_in"))
      (node (ref "IC2") (pin "16") (pinfunction "AVDD_16") (pintype "power_in"))
      (node (ref "IC2") (pin "17") (pinfunction "AVDD_17") (pintype "power_in"))
      (node (ref "IC2") (pin "22") (pinfunction "AVDD_22") (pintype "power_in"))
      (node (ref "IC34") (pin "5") (pinfunction "VOUT_5") (pintype "power_in"))
    )
    (net (code "90") (name "Net-(J1-1)") (class "Default")
      (node (ref "J1") (pin "S") (pinfunction "1_S") (pintype "passive"))
      (node (ref "R23") (pin "2") (pinfunction "2_2") (pintype "passive"))
    )
    (net (code "91") (name "Net-(J2-1)") (class "Default")
      (node (ref "J2") (pin "S") (pinfunction "1_S") (pintype "passive"))
      (node (ref "J3") (pin "S") (pinfunction "1_S") (pintype "passive"))
    )
    (net (code "92") (name "Net-(J4-Pad1)") (class "Default")
      (node (ref "J4") (pin "1") (pinfunction "1_1") (pintype "passive"))
      (node (ref "R24") (pin "2") (pinfunction "2_2") (pintype "passive"))
    )
    (net (code "93") (name "Net-(J5-Pad1)") (class "Default")
      (node (ref "J5") (pin "1") (pinfunction "1_1") (pintype "passive"))
      (node (ref "J6") (pin "1") (pinfunction "1_1") (pintype "passive"))
    )
    (net (code "94") (name "Net-(JP1-Pad2)") (class "Default")
      (node (ref "JP1") (pin "2") (pinfunction "2_2") (pintype "passive"))
      (node (ref "L2") (pin "1") (pinfunction "1_1") (pintype "passive"))
    )
    (net (code "95") (name "Net-(JP5-Pad6)") (class "Default")
      (node (ref "JP5") (pin "6") (pinfunction "6_6") (pintype "passive"))
      (node (ref "X5") (pin "1") (pinfunction "1_1") (pintype "passive"))
    )
    (net (code "96") (name "Net-(JP12-Pad1)") (class "Default")
      (node (ref "JP12") (pin "1") (pinfunction "1_1") (pintype "passive"))
      (node (ref "X10") (pin "1") (pinfunction "1_1") (pintype "passive"))
    )
    (net (code "97") (name "Net-(R21-Pad1)") (class "Default")
      (node (ref "R21") (pin "1") (pinfunction "1_1") (pintype "passive"))
      (node (ref "X1") (pin "1") (pinfunction "1_1") (pintype "passive"))
    )
    (net (code "98") (name "Net-(R22-Pad1)") (class "Default")
      (node (ref "R22") (pin "1") (pinfunction "1_1") (pintype "passive"))
      (node (ref "X2") (pin "1") (pinfunction "1_1") (pintype "passive"))
    )
    (net (code "99") (name "Net-(R49-Pad2)") (class "Default")
      (node (ref "R49") (pin "2") (pinfunction "2_2") (pintype "passive"))
      (node (ref "X10") (pin "2") (pinfunction "2_2") (pintype "passive"))
    )
    (net (code "100") (name "Net-(R50-Pad1)") (class "Default")
      (node (ref "R50") (pin "1") (pinfunction "1_1") (pintype "passive"))
      (node (ref "R51") (pin "2") (pinfunction "2_2") (pintype "passive"))
      (node (ref "X10") (pin "3") (pinfunction "3_3") (pintype "passive"))
    )
    (net (code "101") (name "Net-(T1-IN+)") (class "Default")
      (node (ref "C39") (pin "1") (pinfunction "1_1") (pintype "passive"))
      (node (ref "T1") (pin "3") (pinfunction "IN+_3") (pintype "bidirectional"))
    )
    (net (code "102") (name "Net-(T1-OUT+)") (class "Default")
      (node (ref "C24") (pin "2") (pinfunction "2_2") (pintype "passive"))
      (node (ref "T1") (pin "4") (pinfunction "OUT+_4") (pintype "bidirectional"))
    )
    (net (code "103") (name "Net-(T1-OUT-)") (class "Default")
      (node (ref "C23") (pin "2") (pinfunction "2_2") (pintype "passive"))
      (node (ref "T1") (pin "6") (pinfunction "OUT-_6") (pintype "bidirectional"))
    )
    (net (code "104") (name "OUT0_N") (class "Default")
      (node (ref "IC4") (pin "11") (pinfunction "OUT0B_11") (pintype "output"))
      (node (ref "JP2") (pin "3") (pinfunction "3_3") (pintype "passive"))
    )
    (net (code "105") (name "OUT0_P") (class "Default")
      (node (ref "IC4") (pin "12") (pinfunction "OUT0_12") (pintype "output"))
      (node (ref "JP2") (pin "1") (pinfunction "1_1") (pintype "passive"))
    )
    (net (code "106") (name "OUT1_N") (class "Default")
      (node (ref "IC4") (pin "14") (pinfunction "OUT1B_14") (pintype "output"))
      (node (ref "JP8") (pin "3") (pinfunction "3_3") (pintype "passive"))
    )
    (net (code "107") (name "OUT1_P") (class "Default")
      (node (ref "IC4") (pin "15") (pinfunction "OUT1_15") (pintype "output"))
      (node (ref "JP8") (pin "1") (pinfunction "1_1") (pintype "passive"))
    )
    (net (code "108") (name "OUT4_N") (class "Default")
      (node (ref "IC4") (pin "26") (pinfunction "OUT4B_26") (pintype "output"))
      (node (ref "JP7") (pin "3") (pinfunction "3_3") (pintype "passive"))
    )
    (net (code "109") (name "OUT4_P") (class "Default")
      (node (ref "IC4") (pin "27") (pinfunction "OUT4_27") (pintype "output"))
      (node (ref "JP7") (pin "1") (pinfunction "1_1") (pintype "passive"))
    )
    (net (code "110") (name "OUT5_N") (class "Default")
      (node (ref "IC4") (pin "30") (pinfunction "OUT5B_30") (pintype "output"))
      (node (ref "X9") (pin "1") (pinfunction "1_1") (pintype "passive"))
    )
    (net (code "111") (name "OUT5_P") (class "Default")
      (node (ref "IC4") (pin "31") (pinfunction "OUT5_31") (pintype "output"))
      (node (ref "X8") (pin "1") (pinfunction "1_1") (pintype "passive"))
    )
    (net (code "112") (name "RX") (class "Default")
      (node (ref "IC5") (pin "43") (pinfunction "PB7_43") (pintype "bidirectional"))
      (node (ref "JP10") (pin "3") (pinfunction "3_3") (pintype "passive"))
    )
    (net (code "113") (name "SCL") (class "Default")
      (node (ref "IC4") (pin "9") (pinfunction "SCLK_9") (pintype "input"))
      (node (ref "IC5") (pin "30") (pinfunction "PA9_30") (pintype "bidirectional"))
      (node (ref "JP11") (pin "2") (pinfunction "2_2") (pintype "passive"))
      (node (ref "R47") (pin "1") (pinfunction "1_1") (pintype "passive"))
    )
    (net (code "114") (name "SDA") (class "Default")
      (node (ref "IC4") (pin "10") (pinfunction "SDA_10") (pintype "bidirectional"))
      (node (ref "IC5") (pin "31") (pinfunction "PA10_31") (pintype "bidirectional"))
      (node (ref "JP11") (pin "1") (pinfunction "1_1") (pintype "passive"))
      (node (ref "R48") (pin "1") (pinfunction "1_1") (pintype "passive"))
    )
    (net (code "115") (name "SI5332_IN1") (class "Default")
      (node (ref "IC4") (pin "8") (pinfunction "INPUT1_8") (pintype "input"))
      (node (ref "IC5") (pin "38") (pinfunction "PA15_38") (pintype "bidirectional"))
    )
    (net (code "116") (name "SI5332_IN2") (class "Default")
      (node (ref "IC4") (pin "17") (pinfunction "INPUT2_17") (pintype "input"))
      (node (ref "IC5") (pin "29") (pinfunction "PA8_29") (pintype "bidirectional"))
    )
    (net (code "117") (name "SI5332_IN3") (class "Default")
      (node (ref "IC4") (pin "24") (pinfunction "INPUT3_24") (pintype "input"))
      (node (ref "IC5") (pin "39") (pinfunction "PB3_39") (pintype "bidirectional"))
    )
    (net (code "118") (name "SI5332_IN4") (class "Default")
      (node (ref "IC4") (pin "28") (pinfunction "INPUT4_28") (pintype "input"))
      (node (ref "IC5") (pin "40") (pinfunction "PB4_40") (pintype "bidirectional"))
    )
    (net (code "119") (name "SI5332_IN5") (class "Default")
      (node (ref "IC4") (pin "29") (pinfunction "INPUT5_29") (pintype "input"))
      (node (ref "IC5") (pin "41") (pinfunction "PB5_41") (pintype "bidirectional"))
    )
    (net (code "120") (name "SI5332_VDDO") (class "Default")
      (node (ref "C51") (pin "1") (pinfunction "1_1") (pintype "passive"))
      (node (ref "C52") (pin "1") (pinfunction "1_1") (pintype "passive"))
      (node (ref "C53") (pin "1") (pinfunction "1_1") (pintype "passive"))
      (node (ref "C54") (pin "1") (pinfunction "1_1") (pintype "passive"))
      (node (ref "C55") (pin "1") (pinfunction "1_1") (pintype "passive"))
      (node (ref "C56") (pin "1") (pinfunction "1_1") (pintype "passive"))
      (node (ref "IC4") (pin "13") (pinfunction "VDDO0_13") (pintype "power_in"))
      (node (ref "IC4") (pin "16") (pinfunction "VDDO1_16") (pintype "power_in"))
      (node (ref "IC4") (pin "20") (pinfunction "VDDO2_20") (pintype "power_in"))
      (node (ref "IC4") (pin "23") (pinfunction "VDDO3_23") (pintype "power_in"))
      (node (ref "IC4") (pin "25") (pinfunction "VDDO4_25") (pintype "power_in"))
      (node (ref "IC4") (pin "32") (pinfunction "VDDO5_32") (pintype "power_in"))
      (node (ref "L10") (pin "1") (pinfunction "1_1") (pintype "passive"))
    )
    (net (code "121") (name "STW_HW_PD") (class "Default")
      (node (ref "IC5") (pin "18") (pinfunction "PB0_18") (pintype "bidirectional"))
      (node (ref "JP4") (pin "3") (pinfunction "3_3") (pintype "passive"))
      (node (ref "R18") (pin "2") (pinfunction "2_2") (pintype "passive"))
    )
    (net (code "122") (name "STW_LD_SDO") (class "Default")
      (node (ref "IC5") (pin "16") (pinfunction "PA6_16") (pintype "bidirectional"))
      (node (ref "JP4") (pin "4") (pinfunction "4_4") (pintype "passive"))
      (node (ref "R14") (pin "2") (pinfunction "2_2") (pintype "passive"))
    )
    (net (code "123") (name "STW_LE") (class "Default")
      (node (ref "IC5") (pin "14") (pinfunction "PA4_14") (pintype "bidirectional"))
      (node (ref "JP4") (pin "7") (pinfunction "7_7") (pintype "passive"))
      (node (ref "R16") (pin "2") (pinfunction "2_2") (pintype "passive"))
    )
    (net (code "124") (name "STW_PD_RF1") (class "Default")
      (node (ref "IC5") (pin "19") (pinfunction "PB1_19") (pintype "bidirectional"))
      (node (ref "JP4") (pin "2") (pinfunction "2_2") (pintype "passive"))
      (node (ref "R20") (pin "2") (pinfunction "2_2") (pintype "passive"))
    )
    (net (code "125") (name "STW_REF_N") (class "Default")
      (node (ref "IC4") (pin "18") (pinfunction "OUT2B_18") (pintype "output"))
      (node (ref "JP5") (pin "9") (pinfunction "9_9") (pintype "passive"))
    )
    (net (code "126") (name "STW_REF_P") (class "Default")
      (node (ref "IC4") (pin "19") (pinfunction "OUT2_19") (pintype "output"))
      (node (ref "JP5") (pin "10") (pinfunction "10_10") (pintype "passive"))
    )
    (net (code "127") (name "STW_SCK") (class "Default")
      (node (ref "IC5") (pin "15") (pinfunction "PA5_15") (pintype "bidirectional"))
      (node (ref "JP4") (pin "6") (pinfunction "6_6") (pintype "passive"))
      (node (ref "R10") (pin "2") (pinfunction "2_2") (pintype "passive"))
    )
    (net (code "128") (name "STW_SDI") (class "Default")
      (node (ref "IC5") (pin "17") (pinfunction "PA7_17") (pintype "bidirectional"))
      (node (ref "JP4") (pin "5") (pinfunction "5_5") (pintype "passive"))
      (node (ref "R12") (pin "2") (pinfunction "2_2") (pintype "passive"))
    )
    (net (code "129") (name "TX") (class "Default")
      (node (ref "IC5") (pin "42") (pinfunction "PB6_42") (pintype "bidirectional"))
      (node (ref "JP10") (pin "1") (pinfunction "1_1") (pintype "passive"))
    )
    (net (code "130") (name "VREG_4V5") (class "Default")
      (node (ref "C14") (pin "1") (pinfunction "1_1") (pintype "passive"))
      (node (ref "C5") (pin "1") (pinfunction "1_1") (pintype "passive"))
      (node (ref "C6") (pin "1") (pinfunction "1_1") (pintype "passive"))
      (node (ref "IC1") (pin "16") (pinfunction "VCC_CPOUT_16") (pintype "power_in"))
      (node (ref "IC1") (pin "32") (pinfunction "VCC_RFOUT_32") (pintype "power_in"))
      (node (ref "R1") (pin "2") (pinfunction "2_2") (pintype "passive"))
    )
    (net (code "131") (name "VREG_4V5_DIRECT") (class "Default")
      (node (ref "C15") (pin "1") (pinfunction "1_1") (pintype "passive"))
      (node (ref "C3") (pin "1") (pinfunction "1_1") (pintype "passive"))
      (node (ref "IC1") (pin "2") (pinfunction "VREG_4V5_2") (pintype "output"))
      (node (ref "IC1") (pin "3") (pinfunction "VCC_VCO_CORE_3") (pintype "power_in"))
      (node (ref "R1") (pin "1") (pinfunction "1_1") (pintype "passive"))
    )
    (net (code "132") (name "VREG_DIG") (class "Default")
      (node (ref "C9") (pin "1") (pinfunction "1_1") (pintype "passive"))
      (node (ref "R3") (pin "2") (pinfunction "2_2") (pintype "passive"))
    )
    (net (code "133") (name "VREG_DIG_DIRECT") (class "Default")
      (node (ref "C8") (pin "1") (pinfunction "1_1") (pintype "passive"))
      (node (ref "IC1") (pin "26") (pinfunction "VDD_DSM_NDIV_26") (pintype "power_in"))
      (node (ref "IC1") (pin "27") (pinfunction "VREG_DIG_27") (pintype "output"))
      (node (ref "R3") (pin "1") (pinfunction "1_1") (pintype "passive"))
    )
    (net (code "134") (name "VREG_REF") (class "Default")
      (node (ref "C11") (pin "1") (pinfunction "1_1") (pintype "passive"))
      (node (ref "R4") (pin "2") (pinfunction "2_2") (pintype "passive"))
    )
    (net (code "135") (name "VREG_REF_DIRECT") (class "Default")
      (node (ref "C10") (pin "1") (pinfunction "1_1") (pintype "passive"))
      (node (ref "IC1") (pin "17") (pinfunction "VDD_PFD_17") (pintype "power_in"))
      (node (ref "IC1") (pin "19") (pinfunction "VREG_REF_19") (pintype "output"))
      (node (ref "R4") (pin "1") (pinfunction "1_1") (pintype "passive"))
    )
    (net (code "136") (name "VREG_VCO") (class "Default")
      (node (ref "C12") (pin "1") (pinfunction "1_1") (pintype "passive"))
      (node (ref "R5") (pin "2") (pinfunction "2_2") (pintype "passive"))
    )
    (net (code "137") (name "VREG_VCO_DIRECT") (class "Default")
      (node (ref "C16") (pin "1") (pinfunction "1_1") (pintype "passive"))
      (node (ref "C4") (pin "1") (pinfunction "1_1") (pintype "passive"))
      (node (ref "IC1") (pin "14") (pinfunction "VDD_CP_14") (pintype "power_in"))
      (node (ref "IC1") (pin "8") (pinfunction "VREG_VCO_8") (pintype "output"))
      (node (ref "R5") (pin "1") (pinfunction "1_1") (pintype "passive"))
    )
    (net (code "138") (name "VTUNE") (class "Default")
      (node (ref "C20") (pin "1") (pinfunction "1_1") (pintype "passive"))
      (node (ref "IC1") (pin "11") (pinfunction "VCTRL_11") (pintype "input"))
      (node (ref "R8") (pin "1") (pinfunction "1_1") (pintype "passive"))
    )
    (net (code "139") (name "unconnected-(IC2-SYNC_CLK-Pad9)") (class "Default")
      (node (ref "IC2") (pin "9") (pinfunction "SYNC_CLK_9") (pintype "output"))
    )
    (net (code "140") (name "unconnected-(IC5-PA0-Pad10)") (class "Default")
      (node (ref "IC5") (pin "10") (pinfunction "PA0_10") (pintype "bidirectional"))
    )
    (net (code "141") (name "unconnected-(IC5-PA1-Pad11)") (class "Default")
      (node (ref "IC5") (pin "11") (pinfunction "PA1_11") (pintype "bidirectional"))
    )
    (net (code "142") (name "unconnected-(IC5-PA2-Pad12)") (class "Default")
      (node (ref "IC5") (pin "12") (pinfunction "PA2_12") (pintype "bidirectional"))
    )
    (net (code "143") (name "unconnected-(IC5-PA3-Pad13)") (class "Default")
      (node (ref "IC5") (pin "13") (pinfunction "PA3_13") (pintype "bidirectional"))
    )
    (net (code "144") (name "unconnected-(IC5-PB8-Pad45)") (class "Default")
      (node (ref "IC5") (pin "45") (pinfunction "PB8_45") (pintype "bidirectional"))
    )
    (net (code "145") (name "unconnected-(IC5-PB9-Pad46)") (class "Default")
      (node (ref "IC5") (pin "46") (pinfunction "PB9_46") (pintype "bidirectional"))
    )
    (net (code "146") (name "unconnected-(IC5-PC13-Pad2)") (class "Default")
      (node (ref "IC5") (pin "2") (pinfunction "PC13_2") (pintype "bidirectional"))
    )
    (net (code "147") (name "unconnected-(IC5-PC14-OSC32_IN-Pad3)") (class "Default")
      (node (ref "IC5") (pin "3") (pinfunction "PC14-OSC32_IN_3") (pintype "bidirectional"))
    )
    (net (code "148") (name "unconnected-(IC5-PC15-OSC32_OUT-Pad4)") (class "Default")
      (node (ref "IC5") (pin "4") (pinfunction "PC15-OSC32_OUT_4") (pintype "bidirectional"))
    )
    (net (code "149") (name "unconnected-(IC5-PH0-OSC_IN-Pad5)") (class "Default")
      (node (ref "IC5") (pin "5") (pinfunction "PH0-OSC_IN_5") (pintype "bidirectional"))
    )
    (net (code "150") (name "unconnected-(IC5-PH1_OSC_OUT-Pad6)") (class "Default")
      (node (ref "IC5") (pin "6") (pinfunction "PH1_OSC_OUT_6") (pintype "bidirectional"))
    )
    (net (code "151") (name "unconnected-(X10-Pad4)") (class "Default")
      (node (ref "X10") (pin "4") (pinfunction "4_4") (pintype "passive"))
    )
  )
)
